# betaV2_0.net
KiCad netlist of a schematic drawn in Altium Designer
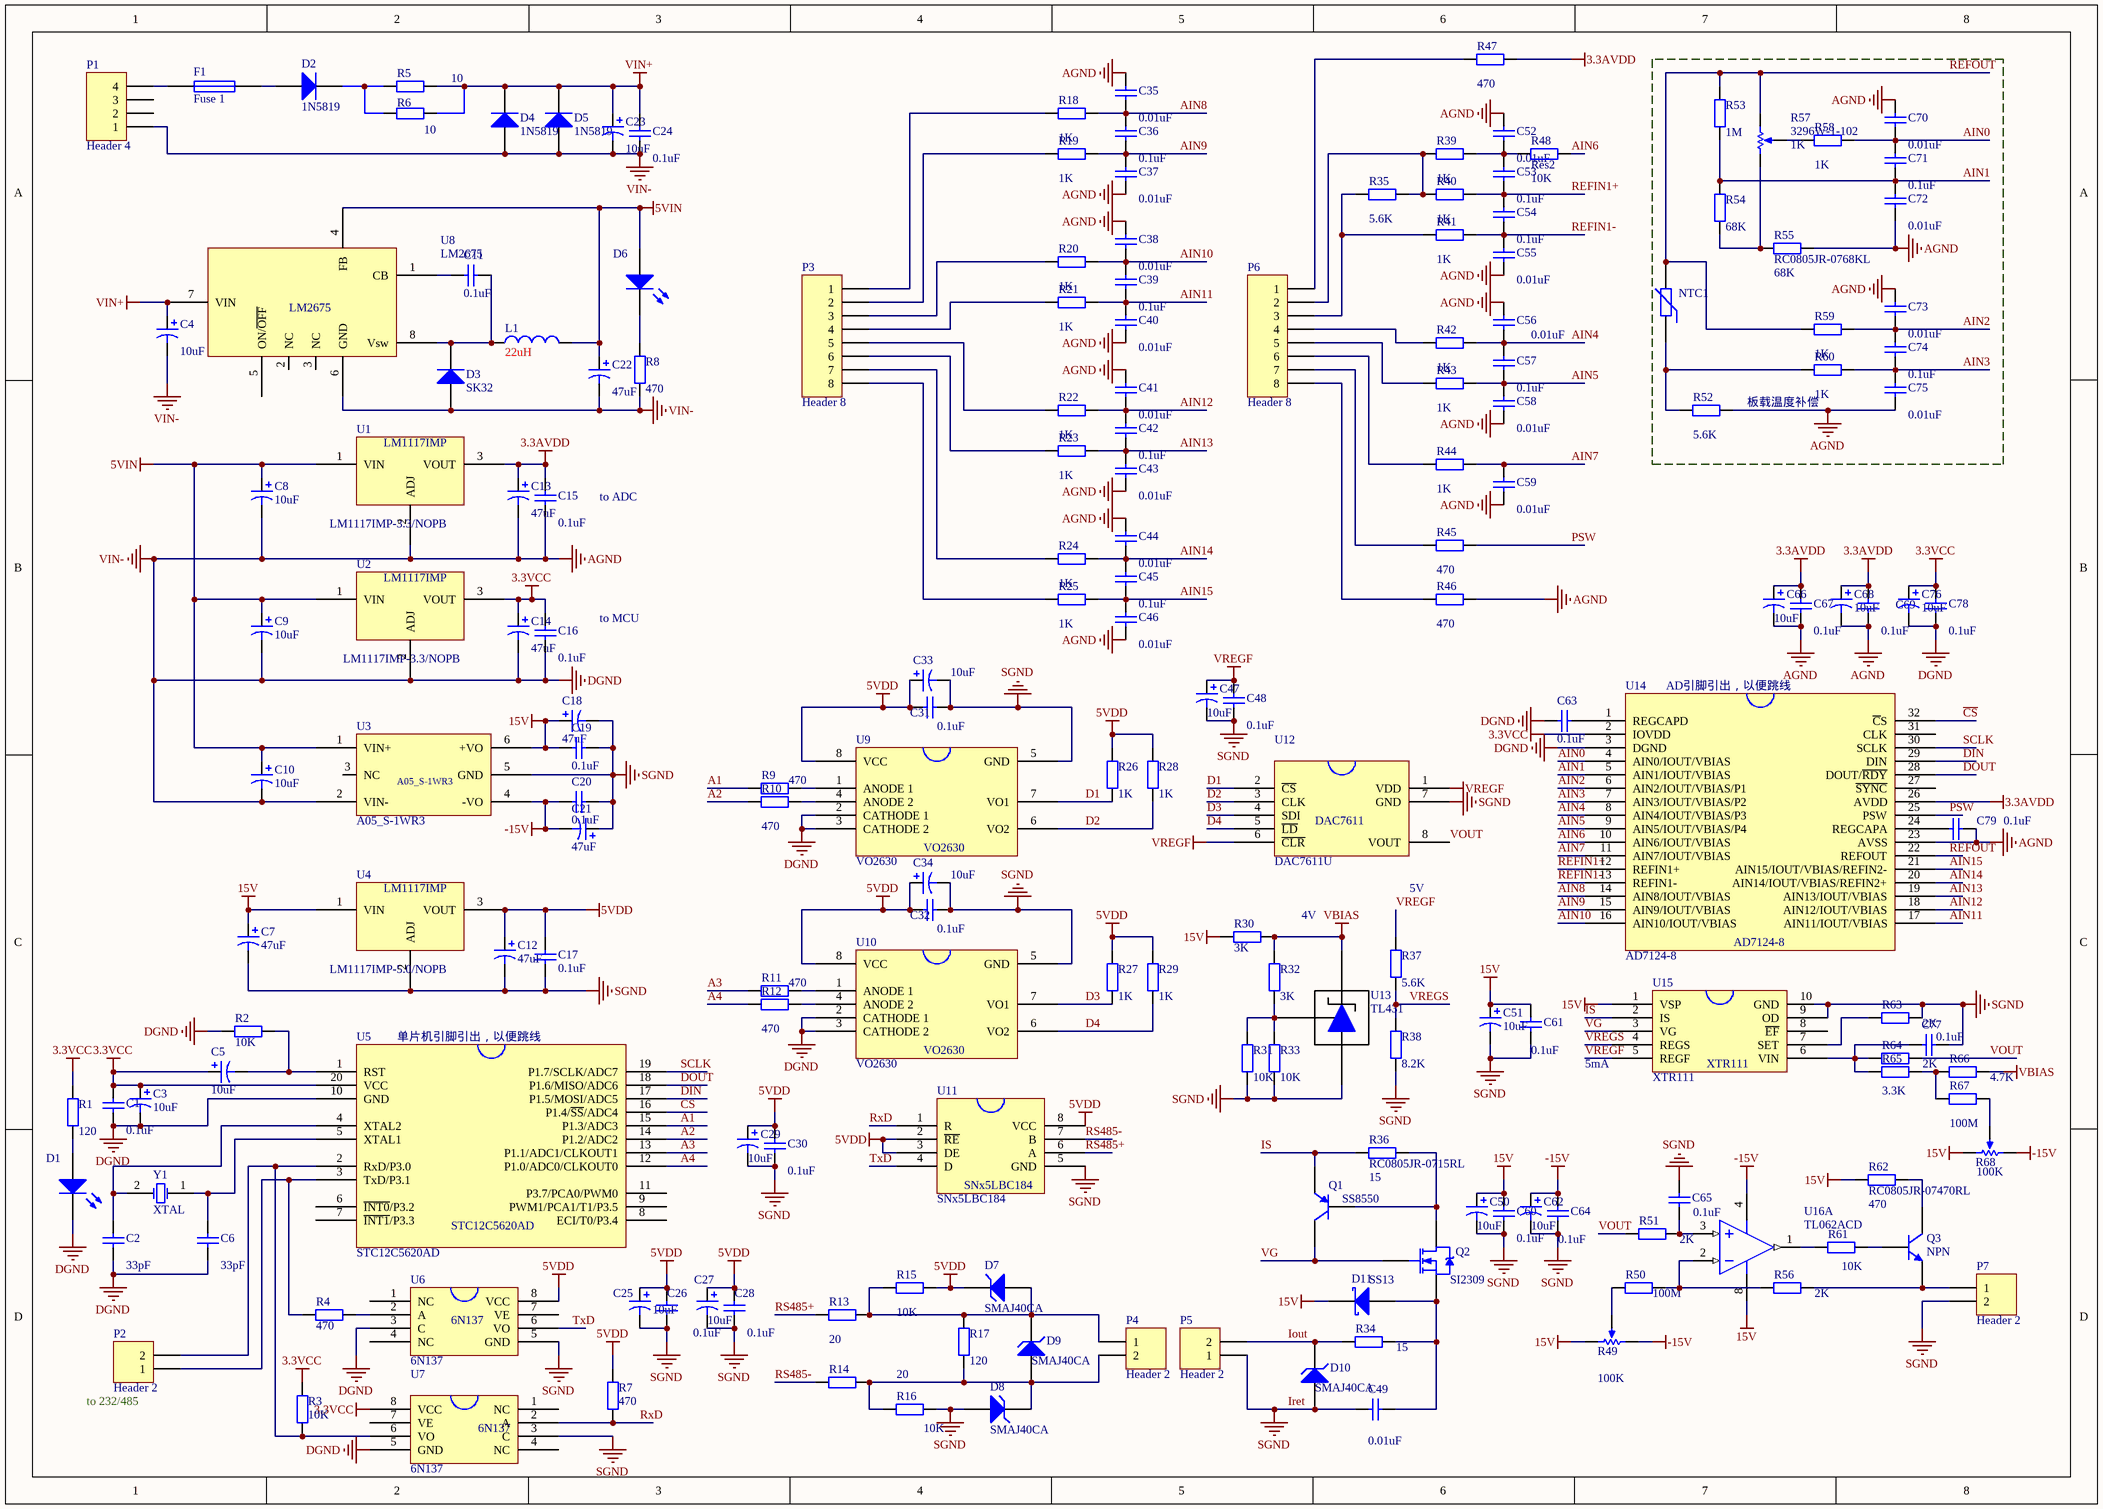
[diagram p0: betaV2.0.SchDoc]

(export (version "E")
  (design (tool "Eeschema 10.0.6"))
  (components
    (comp (ref "C1")
      (value "0.1uF")
      (footprint "0805c")
      (description "Capacitor")
      (fields (field (name "Comment") "CC0805MRX7R9BB104"))
      (libsource (lib "Miscellaneous Devices") (part "Cap"))
    )
    (comp (ref "C2")
      (value "33pF")
      (footprint "0805c")
      (description "Capacitor")
      (fields (field (name "Comment") "CC0805MRX7R9BB330") (field (name "PUBLISHER") "Altium Limited"))
      (libsource (lib "Miscellaneous Devices") (part "Cap"))
    )
    (comp (ref "C3")
      (value "10uF")
      (footprint "CB")
      (description "Polarized Capacitor (Radial)")
      (fields (field (name "Comment") "T494B106M010AHAUTO") (field (name "PUBLISHER") "Altium Limited"))
      (libsource (lib "Miscellaneous Devices") (part "Cap Pol1"))
    )
    (comp (ref "C4")
      (value "10uF")
      (footprint "Φ6.3×11.5")
      (description "Polarized Capacitor (Radial)")
      (fields (field (name "Comment") "ECR1VNP100M1V050011") (field (name "PUBLISHER") "Altium Limited"))
      (libsource (lib "Miscellaneous Devices") (part "Cap Pol1"))
    )
    (comp (ref "C5")
      (value "10uF")
      (footprint "CB")
      (description "Polarized Capacitor (Radial)")
      (fields (field (name "Comment") "T494B106M010AHAUTO") (field (name "PUBLISHER") "Altium Limited"))
      (libsource (lib "Miscellaneous Devices") (part "Cap Pol1"))
    )
    (comp (ref "C6")
      (value "33pF")
      (footprint "0805c")
      (description "Capacitor")
      (fields (field (name "Comment") "CC0805MRX7R9BB330") (field (name "PUBLISHER") "Altium Limited"))
      (libsource (lib "Miscellaneous Devices") (part "Cap"))
    )
    (comp (ref "C7")
      (value "47uF")
      (footprint "CB")
      (description "Polarized Capacitor (Radial)")
      (fields (field (name "Comment") "T494B476K025ATAUTO") (field (name "PUBLISHER") "Altium Limited"))
      (libsource (lib "Miscellaneous Devices") (part "Cap Pol1"))
    )
    (comp (ref "C8")
      (value "10uF")
      (footprint "CB")
      (description "Polarized Capacitor (Radial)")
      (fields (field (name "Comment") "T494B106M010AHAUTO") (field (name "PUBLISHER") "Altium Limited"))
      (libsource (lib "Miscellaneous Devices") (part "Cap Pol1"))
    )
    (comp (ref "C9")
      (value "10uF")
      (footprint "CB")
      (description "Polarized Capacitor (Radial)")
      (fields (field (name "Comment") "T494B106M010AHAUTO") (field (name "PUBLISHER") "Altium Limited"))
      (libsource (lib "Miscellaneous Devices") (part "Cap Pol1"))
    )
    (comp (ref "C10")
      (value "10uF")
      (footprint "CB")
      (description "Polarized Capacitor (Radial)")
      (fields (field (name "Comment") "T494B106M010AHAUTO") (field (name "PUBLISHER") "Altium Limited"))
      (libsource (lib "Miscellaneous Devices") (part "Cap Pol1"))
    )
    (comp (ref "C11")
      (value "0.1uF")
      (footprint "0805c")
      (description "Capacitor")
      (fields (field (name "Comment") "CC0805MRX7R9BB104") (field (name "PUBLISHER") "Altium Limited"))
      (libsource (lib "Miscellaneous Devices") (part "Cap"))
    )
    (comp (ref "C12")
      (value "47uF")
      (footprint "CB")
      (description "Polarized Capacitor (Radial)")
      (fields (field (name "Comment") "T494B476M010AHAUTO") (field (name "PUBLISHER") "Altium Limited"))
      (libsource (lib "Miscellaneous Devices") (part "Cap Pol1"))
    )
    (comp (ref "C13")
      (value "47uF")
      (footprint "CB")
      (description "Polarized Capacitor (Radial)")
      (fields (field (name "Comment") "T494B476M010AHAUTO") (field (name "PUBLISHER") "Altium Limited"))
      (libsource (lib "Miscellaneous Devices") (part "Cap Pol1"))
    )
    (comp (ref "C14")
      (value "47uF")
      (footprint "CB")
      (description "Polarized Capacitor (Radial)")
      (fields (field (name "Comment") "T494B476M010AHAUTO") (field (name "PUBLISHER") "Altium Limited"))
      (libsource (lib "Miscellaneous Devices") (part "Cap Pol1"))
    )
    (comp (ref "C15")
      (value "0.1uF")
      (footprint "0805c")
      (description "Capacitor")
      (fields (field (name "Comment") "CC0805MRX7R9BB104") (field (name "PUBLISHER") "Altium Limited"))
      (libsource (lib "Miscellaneous Devices") (part "Cap"))
    )
    (comp (ref "C16")
      (value "0.1uF")
      (footprint "0805c")
      (description "Capacitor")
      (fields (field (name "Comment") "CC0805MRX7R9BB104") (field (name "PUBLISHER") "Altium Limited"))
      (libsource (lib "Miscellaneous Devices") (part "Cap"))
    )
    (comp (ref "C17")
      (value "0.1uF")
      (footprint "0805c")
      (description "Capacitor")
      (fields (field (name "Comment") "CC0805MRX7R9BB104") (field (name "PUBLISHER") "Altium Limited"))
      (libsource (lib "Miscellaneous Devices") (part "Cap"))
    )
    (comp (ref "C18")
      (value "47uF")
      (footprint "CB")
      (description "Polarized Capacitor (Radial)")
      (fields (field (name "Comment") "T494B476K025ATAUTO") (field (name "PUBLISHER") "Altium Limited"))
      (libsource (lib "Miscellaneous Devices") (part "Cap Pol1"))
    )
    (comp (ref "C19")
      (value "0.1uF")
      (footprint "0805c")
      (description "Capacitor")
      (fields (field (name "Comment") "CC0805MRX7R9BB104") (field (name "PUBLISHER") "Altium Limited"))
      (libsource (lib "Miscellaneous Devices") (part "Cap"))
    )
    (comp (ref "C20")
      (value "0.1uF")
      (footprint "0805c")
      (description "Capacitor")
      (fields (field (name "Comment") "CC0805MRX7R9BB104") (field (name "PUBLISHER") "Altium Limited"))
      (libsource (lib "Miscellaneous Devices") (part "Cap"))
    )
    (comp (ref "C21")
      (value "47uF")
      (footprint "CB")
      (description "Polarized Capacitor (Radial)")
      (fields (field (name "Comment") "T494B476K025ATAUTO") (field (name "PUBLISHER") "Altium Limited"))
      (libsource (lib "Miscellaneous Devices") (part "Cap Pol1"))
    )
    (comp (ref "C22")
      (value "47uF")
      (footprint "CB")
      (description "Polarized Capacitor (Radial)")
      (fields (field (name "Comment") "T494B476M010AHAUTO") (field (name "PUBLISHER") "Altium Limited"))
      (libsource (lib "Miscellaneous Devices") (part "Cap Pol1"))
    )
    (comp (ref "C23")
      (value "10uF")
      (footprint "Φ6.3×11.5")
      (description "Polarized Capacitor (Radial)")
      (fields (field (name "Comment") "ECR1VNP100M1V050011") (field (name "PUBLISHER") "Altium Limited"))
      (libsource (lib "Miscellaneous Devices") (part "Cap Pol1"))
    )
    (comp (ref "C24")
      (value "0.1uF")
      (footprint "0805c")
      (description "Capacitor")
      (fields (field (name "Comment") "CC0805MRX7R9BB104") (field (name "PUBLISHER") "Altium Limited"))
      (libsource (lib "Miscellaneous Devices") (part "Cap"))
    )
    (comp (ref "C25")
      (value "10uF")
      (footprint "CB")
      (description "Polarized Capacitor (Radial)")
      (fields (field (name "Comment") "T494B106M010AHAUTO") (field (name "PUBLISHER") "Altium Limited"))
      (libsource (lib "Miscellaneous Devices") (part "Cap Pol1"))
    )
    (comp (ref "C26")
      (value "0.1uF")
      (footprint "0805c")
      (description "Capacitor")
      (fields (field (name "Comment") "CC0805MRX7R9BB104") (field (name "PUBLISHER") "Altium Limited"))
      (libsource (lib "Miscellaneous Devices") (part "Cap"))
    )
    (comp (ref "C27")
      (value "10uF")
      (footprint "CB")
      (description "Polarized Capacitor (Radial)")
      (fields (field (name "Comment") "T494B106M010AHAUTO") (field (name "PUBLISHER") "Altium Limited"))
      (libsource (lib "Miscellaneous Devices") (part "Cap Pol1"))
    )
    (comp (ref "C28")
      (value "0.1uF")
      (footprint "0805c")
      (description "Capacitor")
      (fields (field (name "Comment") "CC0805MRX7R9BB104") (field (name "PUBLISHER") "Altium Limited"))
      (libsource (lib "Miscellaneous Devices") (part "Cap"))
    )
    (comp (ref "C29")
      (value "10uF")
      (footprint "CB")
      (description "Polarized Capacitor (Radial)")
      (fields (field (name "Comment") "T494B106M010AHAUTO") (field (name "PUBLISHER") "Altium Limited"))
      (libsource (lib "Miscellaneous Devices") (part "Cap Pol1"))
    )
    (comp (ref "C30")
      (value "0.1uF")
      (footprint "0805c")
      (description "Capacitor")
      (fields (field (name "Comment") "CC0805MRX7R9BB104") (field (name "PUBLISHER") "Altium Limited"))
      (libsource (lib "Miscellaneous Devices") (part "Cap"))
    )
    (comp (ref "C31")
      (value "0.1uF")
      (footprint "0805c")
      (description "Capacitor")
      (fields (field (name "Comment") "CC0805MRX7R9BB104") (field (name "PUBLISHER") "Altium Limited"))
      (libsource (lib "Miscellaneous Devices") (part "Cap"))
    )
    (comp (ref "C32")
      (value "0.1uF")
      (footprint "0805c")
      (description "Capacitor")
      (fields (field (name "Comment") "CC0805MRX7R9BB104") (field (name "PUBLISHER") "Altium Limited"))
      (libsource (lib "Miscellaneous Devices") (part "Cap"))
    )
    (comp (ref "C33")
      (value "10uF")
      (footprint "CB")
      (description "Polarized Capacitor (Radial)")
      (fields (field (name "Comment") "T494B106M010AHAUTO") (field (name "PUBLISHER") "Altium Limited"))
      (libsource (lib "Miscellaneous Devices") (part "Cap Pol1"))
    )
    (comp (ref "C34")
      (value "10uF")
      (footprint "CB")
      (description "Polarized Capacitor (Radial)")
      (fields (field (name "Comment") "T494B106M010AHAUTO") (field (name "PUBLISHER") "Altium Limited"))
      (libsource (lib "Miscellaneous Devices") (part "Cap Pol1"))
    )
    (comp (ref "C35")
      (value "0.01uF")
      (footprint "0805c")
      (description "Capacitor")
      (fields (field (name "Comment") "CC0805MRX7R9BB103") (field (name "PUBLISHER") "Altium Limited"))
      (libsource (lib "Miscellaneous Devices") (part "Cap"))
    )
    (comp (ref "C36")
      (value "0.1uF")
      (footprint "0805c")
      (description "Capacitor")
      (fields (field (name "Comment") "CC0805MRX7R9BB104") (field (name "PUBLISHER") "Altium Limited"))
      (libsource (lib "Miscellaneous Devices") (part "Cap"))
    )
    (comp (ref "C37")
      (value "0.01uF")
      (footprint "0805c")
      (description "Capacitor")
      (fields (field (name "Comment") "CC0805MRX7R9BB103") (field (name "PUBLISHER") "Altium Limited"))
      (libsource (lib "Miscellaneous Devices") (part "Cap"))
    )
    (comp (ref "C38")
      (value "0.01uF")
      (footprint "0805c")
      (description "Capacitor")
      (fields (field (name "Comment") "CC0805MRX7R9BB103") (field (name "PUBLISHER") "Altium Limited"))
      (libsource (lib "Miscellaneous Devices") (part "Cap"))
    )
    (comp (ref "C39")
      (value "0.1uF")
      (footprint "0805c")
      (description "Capacitor")
      (fields (field (name "Comment") "CC0805MRX7R9BB104") (field (name "PUBLISHER") "Altium Limited"))
      (libsource (lib "Miscellaneous Devices") (part "Cap"))
    )
    (comp (ref "C40")
      (value "0.01uF")
      (footprint "0805c")
      (description "Capacitor")
      (fields (field (name "Comment") "CC0805MRX7R9BB103") (field (name "PUBLISHER") "Altium Limited"))
      (libsource (lib "Miscellaneous Devices") (part "Cap"))
    )
    (comp (ref "C41")
      (value "0.01uF")
      (footprint "0805c")
      (description "Capacitor")
      (fields (field (name "Comment") "CC0805MRX7R9BB103") (field (name "PUBLISHER") "Altium Limited"))
      (libsource (lib "Miscellaneous Devices") (part "Cap"))
    )
    (comp (ref "C42")
      (value "0.1uF")
      (footprint "0805c")
      (description "Capacitor")
      (fields (field (name "Comment") "CC0805MRX7R9BB104") (field (name "PUBLISHER") "Altium Limited"))
      (libsource (lib "Miscellaneous Devices") (part "Cap"))
    )
    (comp (ref "C43")
      (value "0.01uF")
      (footprint "0805c")
      (description "Capacitor")
      (fields (field (name "Comment") "CC0805MRX7R9BB103") (field (name "PUBLISHER") "Altium Limited"))
      (libsource (lib "Miscellaneous Devices") (part "Cap"))
    )
    (comp (ref "C44")
      (value "0.01uF")
      (footprint "0805c")
      (description "Capacitor")
      (fields (field (name "Comment") "CC0805MRX7R9BB103") (field (name "PUBLISHER") "Altium Limited"))
      (libsource (lib "Miscellaneous Devices") (part "Cap"))
    )
    (comp (ref "C45")
      (value "0.1uF")
      (footprint "0805c")
      (description "Capacitor")
      (fields (field (name "Comment") "CC0805MRX7R9BB104") (field (name "PUBLISHER") "Altium Limited"))
      (libsource (lib "Miscellaneous Devices") (part "Cap"))
    )
    (comp (ref "C46")
      (value "0.01uF")
      (footprint "0805c")
      (description "Capacitor")
      (fields (field (name "Comment") "CC0805MRX7R9BB103") (field (name "PUBLISHER") "Altium Limited"))
      (libsource (lib "Miscellaneous Devices") (part "Cap"))
    )
    (comp (ref "C47")
      (value "10uF")
      (footprint "CB")
      (description "Polarized Capacitor (Radial)")
      (fields (field (name "Comment") "T494B106M010AHAUTO") (field (name "PUBLISHER") "Altium Limited"))
      (libsource (lib "Miscellaneous Devices") (part "Cap Pol1"))
    )
    (comp (ref "C48")
      (value "0.1uF")
      (footprint "0805c")
      (description "Capacitor")
      (fields (field (name "Comment") "CC0805MRX7R9BB104") (field (name "PUBLISHER") "Altium Limited"))
      (libsource (lib "Miscellaneous Devices") (part "Cap"))
    )
    (comp (ref "C49")
      (value "0.01uF")
      (footprint "0805c")
      (description "Capacitor")
      (fields (field (name "Comment") "CC0805MRX7R9BB103") (field (name "PUBLISHER") "Altium Limited"))
      (libsource (lib "Miscellaneous Devices") (part "Cap"))
    )
    (comp (ref "C50")
      (value "10uF")
      (footprint "CB")
      (description "Polarized Capacitor (Radial)")
      (fields (field (name "Comment") "T494B106M025AHAUTO") (field (name "PUBLISHER") "Altium Limited"))
      (libsource (lib "Miscellaneous Devices") (part "Cap Pol1"))
    )
    (comp (ref "C51")
      (value "10uF")
      (footprint "CB")
      (description "Polarized Capacitor (Radial)")
      (fields (field (name "Comment") "T494B106M025AHAUTO") (field (name "PUBLISHER") "Altium Limited"))
      (libsource (lib "Miscellaneous Devices") (part "Cap Pol1"))
    )
    (comp (ref "C52")
      (value "0.01uF")
      (footprint "0805c")
      (description "Capacitor")
      (fields (field (name "Comment") "CC0805MRX7R9BB103") (field (name "PUBLISHER") "Altium Limited"))
      (libsource (lib "Miscellaneous Devices") (part "Cap"))
    )
    (comp (ref "C53")
      (value "0.1uF")
      (footprint "0805c")
      (description "Capacitor")
      (fields (field (name "Comment") "CC0805MRX7R9BB104") (field (name "PUBLISHER") "Altium Limited"))
      (libsource (lib "Miscellaneous Devices") (part "Cap"))
    )
    (comp (ref "C54")
      (value "0.1uF")
      (footprint "0805c")
      (description "Capacitor")
      (fields (field (name "Comment") "CC0805MRX7R9BB104") (field (name "PUBLISHER") "Altium Limited"))
      (libsource (lib "Miscellaneous Devices") (part "Cap"))
    )
    (comp (ref "C55")
      (value "0.01uF")
      (footprint "0805c")
      (description "Capacitor")
      (fields (field (name "Comment") "CC0805MRX7R9BB103") (field (name "PUBLISHER") "Altium Limited"))
      (libsource (lib "Miscellaneous Devices") (part "Cap"))
    )
    (comp (ref "C56")
      (value "0.01uF")
      (footprint "0805c")
      (description "Capacitor")
      (fields (field (name "Comment") "CC0805MRX7R9BB103") (field (name "PUBLISHER") "Altium Limited"))
      (libsource (lib "Miscellaneous Devices") (part "Cap"))
    )
    (comp (ref "C57")
      (value "0.1uF")
      (footprint "0805c")
      (description "Capacitor")
      (fields (field (name "Comment") "CC0805MRX7R9BB104") (field (name "PUBLISHER") "Altium Limited"))
      (libsource (lib "Miscellaneous Devices") (part "Cap"))
    )
    (comp (ref "C58")
      (value "0.01uF")
      (footprint "0805c")
      (description "Capacitor")
      (fields (field (name "Comment") "CC0805MRX7R9BB103") (field (name "PUBLISHER") "Altium Limited"))
      (libsource (lib "Miscellaneous Devices") (part "Cap"))
    )
    (comp (ref "C59")
      (value "0.01uF")
      (footprint "0805c")
      (description "Capacitor")
      (fields (field (name "Comment") "CC0805MRX7R9BB103") (field (name "PUBLISHER") "Altium Limited"))
      (libsource (lib "Miscellaneous Devices") (part "Cap"))
    )
    (comp (ref "C60")
      (value "0.1uF")
      (footprint "0805c")
      (description "Capacitor")
      (fields (field (name "Comment") "CC0805MRX7R9BB104") (field (name "PUBLISHER") "Altium Limited"))
      (libsource (lib "Miscellaneous Devices") (part "Cap"))
    )
    (comp (ref "C61")
      (value "0.1uF")
      (footprint "0805c")
      (description "Capacitor")
      (fields (field (name "Comment") "CC0805MRX7R9BB104") (field (name "PUBLISHER") "Altium Limited"))
      (libsource (lib "Miscellaneous Devices") (part "Cap"))
    )
    (comp (ref "C62")
      (value "10uF")
      (footprint "CB")
      (description "Polarized Capacitor (Radial)")
      (fields (field (name "Comment") "T494B106M025AHAUTO") (field (name "PUBLISHER") "Altium Limited"))
      (libsource (lib "Miscellaneous Devices") (part "Cap Pol1"))
    )
    (comp (ref "C63")
      (value "0.1uF")
      (footprint "0805c")
      (description "Capacitor")
      (fields (field (name "Comment") "CC0805MRX7R9BB104") (field (name "PUBLISHER") "Altium Limited"))
      (libsource (lib "Miscellaneous Devices") (part "Cap"))
    )
    (comp (ref "C64")
      (value "0.1uF")
      (footprint "0805c")
      (description "Capacitor")
      (fields (field (name "Comment") "CC0805MRX7R9BB104") (field (name "PUBLISHER") "Altium Limited"))
      (libsource (lib "Miscellaneous Devices") (part "Cap"))
    )
    (comp (ref "C65")
      (value "0.1uF")
      (footprint "0805c")
      (description "Capacitor")
      (fields (field (name "Comment") "CC0805MRX7R9BB104") (field (name "PUBLISHER") "Altium Limited"))
      (libsource (lib "Miscellaneous Devices") (part "Cap"))
    )
    (comp (ref "C66")
      (value "10uF")
      (footprint "CB")
      (description "Polarized Capacitor (Radial)")
      (fields (field (name "Comment") "T494B106M010AHAUTO") (field (name "PUBLISHER") "Altium Limited"))
      (libsource (lib "Miscellaneous Devices") (part "Cap Pol1"))
    )
    (comp (ref "C67")
      (value "0.1uF")
      (footprint "0805c")
      (description "Capacitor")
      (fields (field (name "Comment") "CC0805MRX7R9BB104") (field (name "PUBLISHER") "Altium Limited"))
      (libsource (lib "Miscellaneous Devices") (part "Cap"))
    )
    (comp (ref "C68")
      (value "10uF")
      (footprint "CB")
      (description "Polarized Capacitor (Radial)")
      (fields (field (name "Comment") "T494B106M010AHAUTO") (field (name "PUBLISHER") "Altium Limited"))
      (libsource (lib "Miscellaneous Devices") (part "Cap Pol1"))
    )
    (comp (ref "C69")
      (value "0.1uF")
      (footprint "0805c")
      (description "Capacitor")
      (fields (field (name "Comment") "CC0805MRX7R9BB104") (field (name "PUBLISHER") "Altium Limited"))
      (libsource (lib "Miscellaneous Devices") (part "Cap"))
    )
    (comp (ref "C70")
      (value "0.01uF")
      (footprint "0805c")
      (description "Capacitor")
      (fields (field (name "Comment") "CC0805MRX7R9BB103") (field (name "PUBLISHER") "Altium Limited"))
      (libsource (lib "Miscellaneous Devices") (part "Cap"))
    )
    (comp (ref "C71")
      (value "0.1uF")
      (footprint "0805c")
      (description "Capacitor")
      (fields (field (name "Comment") "CC0805MRX7R9BB104") (field (name "PUBLISHER") "Altium Limited"))
      (libsource (lib "Miscellaneous Devices") (part "Cap"))
    )
    (comp (ref "C72")
      (value "0.01uF")
      (footprint "0805c")
      (description "Capacitor")
      (fields (field (name "Comment") "CC0805MRX7R9BB103") (field (name "PUBLISHER") "Altium Limited"))
      (libsource (lib "Miscellaneous Devices") (part "Cap"))
    )
    (comp (ref "C73")
      (value "0.01uF")
      (footprint "0805c")
      (description "Capacitor")
      (fields (field (name "Comment") "CC0805MRX7R9BB103") (field (name "PUBLISHER") "Altium Limited"))
      (libsource (lib "Miscellaneous Devices") (part "Cap"))
    )
    (comp (ref "C74")
      (value "0.1uF")
      (footprint "0805c")
      (description "Capacitor")
      (fields (field (name "Comment") "CC0805MRX7R9BB104") (field (name "PUBLISHER") "Altium Limited"))
      (libsource (lib "Miscellaneous Devices") (part "Cap"))
    )
    (comp (ref "C75")
      (value "0.01uF")
      (footprint "0805c")
      (description "Capacitor")
      (fields (field (name "Comment") "CC0805MRX7R9BB103") (field (name "PUBLISHER") "Altium Limited"))
      (libsource (lib "Miscellaneous Devices") (part "Cap"))
    )
    (comp (ref "C76")
      (value "10uF")
      (footprint "CB")
      (description "Polarized Capacitor (Radial)")
      (fields (field (name "Comment") "T494B106M010AHAUTO") (field (name "PUBLISHER") "Altium Limited"))
      (libsource (lib "Miscellaneous Devices") (part "Cap Pol1"))
    )
    (comp (ref "C77")
      (value "0.1uF")
      (footprint "0805c")
      (description "Capacitor")
      (fields (field (name "Comment") "CC0805MRX7R9BB104") (field (name "PUBLISHER") "Altium Limited"))
      (libsource (lib "Miscellaneous Devices") (part "Cap"))
    )
    (comp (ref "C78")
      (value "0.1uF")
      (footprint "0805c")
      (description "Capacitor")
      (fields (field (name "Comment") "CC0805MRX7R9BB104") (field (name "PUBLISHER") "Altium Limited"))
      (libsource (lib "Miscellaneous Devices") (part "Cap"))
    )
    (comp (ref "C79")
      (value "0.1uF")
      (footprint "0805c")
      (description "Capacitor")
      (fields (field (name "Comment") "CC0805MRX7R9BB104") (field (name "PUBLISHER") "Altium Limited"))
      (libsource (lib "Miscellaneous Devices") (part "Cap"))
    )
    (comp (ref "D1")
      (value "150080GS75000")
      (footprint "6-0805_N")
      (description "Typical RED, GREEN, YELLOW, AMBER GaAs LED")
      (fields (field (name "PUBLISHER") "Altium Limited"))
      (libsource (lib "Miscellaneous Devices") (part "LED2"))
    )
    (comp (ref "D2")
      (value "1N5819")
      (footprint "SMC")
      (description "Default Diode")
      (fields (field (name "PUBLISHER") "Altium Limited"))
      (libsource (lib "Miscellaneous Devices") (part "Diode"))
    )
    (comp (ref "D3")
      (value "SK32")
      (footprint "SMC")
      (description "Default Diode")
      (fields (field (name "PUBLISHER") "Altium Limited"))
      (libsource (lib "Miscellaneous Devices") (part "Diode"))
    )
    (comp (ref "D4")
      (value "1N5819")
      (footprint "SMC")
      (description "Default Diode")
      (fields (field (name "PUBLISHER") "Altium Limited"))
      (libsource (lib "Miscellaneous Devices") (part "Diode"))
    )
    (comp (ref "D5")
      (value "1N5819")
      (footprint "SMC")
      (description "Default Diode")
      (fields (field (name "PUBLISHER") "Altium Limited"))
      (libsource (lib "Miscellaneous Devices") (part "Diode"))
    )
    (comp (ref "D6")
      (value "150080GS75000")
      (footprint "LEDΦ3.0")
      (description "Typical RED, GREEN, YELLOW, AMBER GaAs LED")
      (fields (field (name "PUBLISHER") "Altium Limited"))
      (libsource (lib "Miscellaneous Devices") (part "LED2"))
    )
    (comp (ref "D7")
      (value "SMAJ40CA")
      (footprint "SMB")
      (description "Zener Diode")
      (fields (field (name "PUBLISHER") "Altium Limited"))
      (libsource (lib "Miscellaneous Devices") (part "D Zener"))
    )
    (comp (ref "D8")
      (value "SMAJ40CA")
      (footprint "SMB")
      (description "Zener Diode")
      (fields (field (name "PUBLISHER") "Altium Limited"))
      (libsource (lib "Miscellaneous Devices") (part "D Zener"))
    )
    (comp (ref "D9")
      (value "SMAJ40CA")
      (footprint "SMB")
      (description "Zener Diode")
      (fields (field (name "PUBLISHER") "Altium Limited"))
      (libsource (lib "Miscellaneous Devices") (part "D Zener"))
    )
    (comp (ref "D10")
      (value "SMAJ40CA")
      (footprint "SMB")
      (description "Zener Diode")
      (fields (field (name "PUBLISHER") "Altium Limited"))
      (libsource (lib "Miscellaneous Devices") (part "D Zener"))
    )
    (comp (ref "D11")
      (value "SS13")
      (footprint "SMB")
      (description "Schottky Diode")
      (fields (field (name "PUBLISHER") "Altium Limited"))
      (libsource (lib "Miscellaneous Devices") (part "D Schottky"))
    )
    (comp (ref "F1")
      (value "Fuse 1")
      (footprint "6-0805_L")
      (description "Fuse")
      (fields (field (name "PUBLISHER") "Altium Limited"))
      (libsource (lib "Miscellaneous Devices") (part "Fuse 1"))
    )
    (comp (ref "L1")
      (value "22uH")
      (footprint "vls4012")
      (fields (field (name "Comment") "VLS4012HBX-220M"))
      (libsource (lib "Miscellaneous Devices") (part "Inductor"))
    )
    (comp (ref "NTC1")
      (value "NTCS0805E3103JHT")
      (footprint "6-0805_N")
      (description "Varistor (Voltage-Sensitive Resistor)")
      (fields (field (name "PUBLISHER") "Altium Limited"))
      (libsource (lib "Miscellaneous Devices") (part "Res Varistor"))
    )
    (comp (ref "P1")
      (value "Header 4")
      (footprint "HDR1X4")
      (description "Header, 4-Pin")
      (fields (field (name "PUBLISHER") "Altium Limited"))
      (libsource (lib "Miscellaneous Connectors") (part "Header 4"))
    )
    (comp (ref "P2")
      (value "Header 2")
      (footprint "HDR1X2")
      (description "Header, 2-Pin")
      (fields (field (name "PUBLISHER") "Altium Limited"))
      (libsource (lib "") (part "Header 2_1"))
    )
    (comp (ref "P3")
      (value "Header 8")
      (footprint "HDR1X8")
      (description "Header, 8-Pin")
      (fields (field (name "PUBLISHER") "Altium Limited"))
      (libsource (lib "Miscellaneous Connectors") (part "Header 8"))
    )
    (comp (ref "P4")
      (value "Header 2")
      (footprint "HDR1X2")
      (description "Header, 2-Pin")
      (fields (field (name "PUBLISHER") "Altium Limited"))
      (libsource (lib "Miscellaneous Connectors") (part "Header 2"))
    )
    (comp (ref "P5")
      (value "Header 2")
      (footprint "HDR1X2")
      (description "Header, 2-Pin")
      (fields (field (name "PUBLISHER") "Altium Limited"))
      (libsource (lib "") (part "Header 2_1"))
    )
    (comp (ref "P6")
      (value "Header 8")
      (footprint "HDR1X8")
      (description "Header, 8-Pin")
      (fields (field (name "PUBLISHER") "Altium Limited"))
      (libsource (lib "Miscellaneous Connectors") (part "Header 8"))
    )
    (comp (ref "P7")
      (value "Header 2")
      (footprint "HDR1X2")
      (description "Header, 2-Pin")
      (fields (field (name "PUBLISHER") "Altium Limited"))
      (libsource (lib "Miscellaneous Connectors") (part "Header 2"))
    )
    (comp (ref "Q1")
      (value "SS8550")
      (footprint "SOT-23-BJT")
      (description "PNP Bipolar Transistor")
      (fields (field (name "PUBLISHER") "Altium Limited"))
      (libsource (lib "Miscellaneous Devices") (part "PNP"))
    )
    (comp (ref "Q2")
      (value "SI2309")
      (footprint "SOT-23-MOS")
      (description "N-Channel Power MOSFET")
      (fields (field (name "PUBLISHER") "Altium Limited"))
      (libsource (lib "Miscellaneous Devices") (part "NMOS-2"))
    )
    (comp (ref "Q3")
      (value "NPN")
      (footprint "SOT-23-BJT")
      (description "NPN Bipolar Transistor")
      (fields (field (name "PUBLISHER") "Altium Limited"))
      (libsource (lib "Miscellaneous Devices") (part "NPN"))
    )
    (comp (ref "R1")
      (value "120")
      (footprint "0805R")
      (description "Resistor")
      (fields (field (name "Comment") "RC0805JR-07120RL") (field (name "PUBLISHER") "Altium Limited"))
      (libsource (lib "") (part "Res2_1"))
    )
    (comp (ref "R2")
      (value "10K")
      (footprint "0805R")
      (description "Resistor")
      (fields (field (name "Comment") "RC0805JR-0710KL") (field (name "PUBLISHER") "Altium Limited"))
      (libsource (lib "") (part "Res2_3"))
    )
    (comp (ref "R3")
      (value "10K")
      (footprint "0805R")
      (description "Resistor")
      (fields (field (name "Comment") "RC0805JR-0710KRL") (field (name "PUBLISHER") "Altium Limited"))
      (libsource (lib "") (part "Res2_2"))
    )
    (comp (ref "R4")
      (value "470")
      (footprint "0805R")
      (description "Resistor")
      (fields (field (name "Comment") "RC0805JR-07470RL") (field (name "PUBLISHER") "Altium Limited"))
      (libsource (lib "") (part "Res2_3"))
    )
    (comp (ref "R5")
      (value "10")
      (footprint "0805R")
      (description "Resistor")
      (fields (field (name "Comment") "PNP-200KJBJ26-10R") (field (name "PUBLISHER") "Altium Limited"))
      (libsource (lib "Miscellaneous Devices") (part "Res2"))
    )
    (comp (ref "R6")
      (value "10")
      (footprint "0805R")
      (description "Resistor")
      (fields (field (name "Comment") "PNP-200KJBJ26-10R") (field (name "PUBLISHER") "Altium Limited"))
      (libsource (lib "Miscellaneous Devices") (part "Res2"))
    )
    (comp (ref "R7")
      (value "470")
      (footprint "0805R")
      (description "Resistor")
      (fields (field (name "Comment") "RC0805JR-07470RL") (field (name "PUBLISHER") "Altium Limited"))
      (libsource (lib "") (part "Res2_2"))
    )
    (comp (ref "R8")
      (value "470")
      (footprint "0805R")
      (description "Resistor")
      (fields (field (name "Comment") "RC0805JR-07470RL") (field (name "PUBLISHER") "Altium Limited"))
      (libsource (lib "") (part "Res2_2"))
    )
    (comp (ref "R9")
      (value "470")
      (footprint "0805R")
      (description "Resistor")
      (fields (field (name "Comment") "RC0805JR-07470RL") (field (name "PUBLISHER") "Altium Limited"))
      (libsource (lib "Miscellaneous Devices") (part "Res2"))
    )
    (comp (ref "R10")
      (value "470")
      (footprint "0805R")
      (description "Resistor")
      (fields (field (name "Comment") "RC0805JR-07470RL") (field (name "PUBLISHER") "Altium Limited"))
      (libsource (lib "Miscellaneous Devices") (part "Res2"))
    )
    (comp (ref "R11")
      (value "470")
      (footprint "0805R")
      (description "Resistor")
      (fields (field (name "Comment") "RC0805JR-07470RL") (field (name "PUBLISHER") "Altium Limited"))
      (libsource (lib "Miscellaneous Devices") (part "Res2"))
    )
    (comp (ref "R12")
      (value "470")
      (footprint "0805R")
      (description "Resistor")
      (fields (field (name "Comment") "RC0805JR-07470RL") (field (name "PUBLISHER") "Altium Limited"))
      (libsource (lib "Miscellaneous Devices") (part "Res2"))
    )
    (comp (ref "R13")
      (value "20")
      (footprint "0805R")
      (description "Resistor")
      (fields (field (name "Comment") "RC0805JR-0720RL") (field (name "PUBLISHER") "Altium Limited"))
      (libsource (lib "") (part "Res2_3"))
    )
    (comp (ref "R14")
      (value "20")
      (footprint "0805R")
      (description "Resistor")
      (fields (field (name "Comment") "RC0805JR-0720RL") (field (name "PUBLISHER") "Altium Limited"))
      (libsource (lib "Miscellaneous Devices") (part "Res2"))
    )
    (comp (ref "R15")
      (value "10K")
      (footprint "0805R")
      (description "Resistor")
      (fields (field (name "Comment") "RC0805JR-0710KL") (field (name "PUBLISHER") "Altium Limited"))
      (libsource (lib "Miscellaneous Devices") (part "Res2"))
    )
    (comp (ref "R16")
      (value "10K")
      (footprint "0805R")
      (description "Resistor")
      (fields (field (name "Comment") "RC0805JR-0710KL") (field (name "PUBLISHER") "Altium Limited"))
      (libsource (lib "Miscellaneous Devices") (part "Res2"))
    )
    (comp (ref "R17")
      (value "120")
      (footprint "0805R")
      (description "Resistor")
      (fields (field (name "Comment") "RC0805JR-07120RL") (field (name "PUBLISHER") "Altium Limited"))
      (libsource (lib "") (part "Res2_2"))
    )
    (comp (ref "R18")
      (value "1K")
      (footprint "0805R")
      (description "Resistor")
      (fields (field (name "Comment") "RC0805JR-071KL") (field (name "PUBLISHER") "Altium Limited"))
      (libsource (lib "Miscellaneous Devices") (part "Res2"))
    )
    (comp (ref "R19")
      (value "1K")
      (footprint "0805R")
      (description "Resistor")
      (fields (field (name "Comment") "RC0805JR-071KL") (field (name "PUBLISHER") "Altium Limited"))
      (libsource (lib "Miscellaneous Devices") (part "Res2"))
    )
    (comp (ref "R20")
      (value "1K")
      (footprint "0805R")
      (description "Resistor")
      (fields (field (name "Comment") "RC0805JR-071KL") (field (name "PUBLISHER") "Altium Limited"))
      (libsource (lib "Miscellaneous Devices") (part "Res2"))
    )
    (comp (ref "R21")
      (value "1K")
      (footprint "0805R")
      (description "Resistor")
      (fields (field (name "Comment") "RC0805JR-071KL") (field (name "PUBLISHER") "Altium Limited"))
      (libsource (lib "Miscellaneous Devices") (part "Res2"))
    )
    (comp (ref "R22")
      (value "1K")
      (footprint "0805R")
      (description "Resistor")
      (fields (field (name "Comment") "RC0805JR-071KL") (field (name "PUBLISHER") "Altium Limited"))
      (libsource (lib "Miscellaneous Devices") (part "Res2"))
    )
    (comp (ref "R23")
      (value "1K")
      (footprint "0805R")
      (description "Resistor")
      (fields (field (name "Comment") "RC0805JR-071KL") (field (name "PUBLISHER") "Altium Limited"))
      (libsource (lib "Miscellaneous Devices") (part "Res2"))
    )
    (comp (ref "R24")
      (value "1K")
      (footprint "0805R")
      (description "Resistor")
      (fields (field (name "Comment") "RC0805JR-071KL") (field (name "PUBLISHER") "Altium Limited"))
      (libsource (lib "Miscellaneous Devices") (part "Res2"))
    )
    (comp (ref "R25")
      (value "1K")
      (footprint "0805R")
      (description "Resistor")
      (fields (field (name "Comment") "RC0805JR-071KL") (field (name "PUBLISHER") "Altium Limited"))
      (libsource (lib "Miscellaneous Devices") (part "Res2"))
    )
    (comp (ref "R26")
      (value "1K")
      (footprint "0805R")
      (description "Resistor")
      (fields (field (name "Comment") "RC0805JR-071KL") (field (name "PUBLISHER") "Altium Limited"))
      (libsource (lib "") (part "Res2_1"))
    )
    (comp (ref "R27")
      (value "1K")
      (footprint "0805R")
      (description "Resistor")
      (fields (field (name "Comment") "RC0805JR-071KL") (field (name "PUBLISHER") "Altium Limited"))
      (libsource (lib "") (part "Res2_1"))
    )
    (comp (ref "R28")
      (value "1K")
      (footprint "0805R")
      (description "Resistor")
      (fields (field (name "Comment") "RC0805JR-071KL") (field (name "PUBLISHER") "Altium Limited"))
      (libsource (lib "") (part "Res2_1"))
    )
    (comp (ref "R29")
      (value "1K")
      (footprint "0805R")
      (description "Resistor")
      (fields (field (name "Comment") "RC0805JR-071KL") (field (name "PUBLISHER") "Altium Limited"))
      (libsource (lib "") (part "Res2_1"))
    )
    (comp (ref "R30")
      (value "3K")
      (footprint "0805R")
      (description "Resistor")
      (fields (field (name "Comment") "RC0805JR-073KL") (field (name "PUBLISHER") "Altium Limited"))
      (libsource (lib "") (part "Res2_3"))
    )
    (comp (ref "R31")
      (value "10K")
      (footprint "0805R")
      (description "Resistor")
      (fields (field (name "Comment") "RC0805JR-0710KL") (field (name "PUBLISHER") "Altium Limited"))
      (libsource (lib "") (part "Res2_1"))
    )
    (comp (ref "R32")
      (value "3K")
      (footprint "0805R")
      (description "Resistor")
      (fields (field (name "Comment") "RC0805JR-073KL") (field (name "PUBLISHER") "Altium Limited"))
      (libsource (lib "") (part "Res2_1"))
    )
    (comp (ref "R33")
      (value "10K")
      (footprint "0805R")
      (description "Resistor")
      (fields (field (name "Comment") "RC0805JR-0710KL") (field (name "PUBLISHER") "Altium Limited"))
      (libsource (lib "") (part "Res2_1"))
    )
    (comp (ref "R34")
      (value "15")
      (footprint "0805R")
      (description "Resistor")
      (fields (field (name "Comment") "RC0805JR-0715RL") (field (name "PUBLISHER") "Altium Limited"))
      (libsource (lib "") (part "Res2_3"))
    )
    (comp (ref "R35")
      (value "5.6K")
      (footprint "0805R")
      (description "Resistor")
      (fields (field (name "Comment") "RC0805JR-075600RL") (field (name "PUBLISHER") "Altium Limited"))
      (libsource (lib "") (part "Res2_3"))
    )
    (comp (ref "R36")
      (value "RC0805JR-0715RL")
      (footprint "0805R")
      (description "Resistor")
      (fields (field (name "ALTIUM_VALUE") "15") (field (name "PUBLISHER") "Altium Limited"))
      (libsource (lib "Miscellaneous Devices") (part "Res2"))
    )
    (comp (ref "R37")
      (value "5.6K")
      (footprint "0805R")
      (description "Resistor")
      (fields (field (name "Comment") "RC0805JR-075600RL") (field (name "PUBLISHER") "Altium Limited"))
      (libsource (lib "") (part "Res2_1"))
    )
    (comp (ref "R38")
      (value "8.2K")
      (footprint "0805R")
      (description "Resistor")
      (fields (field (name "Comment") "RC0805JR-078200RL") (field (name "PUBLISHER") "Altium Limited"))
      (libsource (lib "") (part "Res2_1"))
    )
    (comp (ref "R39")
      (value "1K")
      (footprint "0805R")
      (description "Resistor")
      (fields (field (name "Comment") "RC0805JR-071KL") (field (name "PUBLISHER") "Altium Limited"))
      (libsource (lib "Miscellaneous Devices") (part "Res2"))
    )
    (comp (ref "R40")
      (value "1K")
      (footprint "0805R")
      (description "Resistor")
      (fields (field (name "Comment") "RC0805JR-071KL") (field (name "PUBLISHER") "Altium Limited"))
      (libsource (lib "Miscellaneous Devices") (part "Res2"))
    )
    (comp (ref "R41")
      (value "1K")
      (footprint "0805R")
      (description "Resistor")
      (fields (field (name "Comment") "RC0805JR-071KL") (field (name "PUBLISHER") "Altium Limited"))
      (libsource (lib "Miscellaneous Devices") (part "Res2"))
    )
    (comp (ref "R42")
      (value "1K")
      (footprint "0805R")
      (description "Resistor")
      (fields (field (name "Comment") "RC0805JR-071KL") (field (name "PUBLISHER") "Altium Limited"))
      (libsource (lib "Miscellaneous Devices") (part "Res2"))
    )
    (comp (ref "R43")
      (value "1K")
      (footprint "0805R")
      (description "Resistor")
      (fields (field (name "Comment") "RC0805JR-071KL") (field (name "PUBLISHER") "Altium Limited"))
      (libsource (lib "Miscellaneous Devices") (part "Res2"))
    )
    (comp (ref "R44")
      (value "1K")
      (footprint "0805R")
      (description "Resistor")
      (fields (field (name "Comment") "RC0805JR-071KL") (field (name "PUBLISHER") "Altium Limited"))
      (libsource (lib "Miscellaneous Devices") (part "Res2"))
    )
    (comp (ref "R45")
      (value "470")
      (footprint "0805R")
      (description "Resistor")
      (fields (field (name "Comment") "RC0805JR-07470RL") (field (name "PUBLISHER") "Altium Limited"))
      (libsource (lib "Miscellaneous Devices") (part "Res2"))
    )
    (comp (ref "R46")
      (value "470")
      (footprint "0805R")
      (description "Resistor")
      (fields (field (name "Comment") "RC0805JR-07470RL") (field (name "PUBLISHER") "Altium Limited"))
      (libsource (lib "Miscellaneous Devices") (part "Res2"))
    )
    (comp (ref "R47")
      (value "470")
      (footprint "0805R")
      (description "Resistor")
      (fields (field (name "Comment") "RC0805JR-07470RL") (field (name "PUBLISHER") "Altium Limited"))
      (libsource (lib "Miscellaneous Devices") (part "Res2"))
    )
    (comp (ref "R48")
      (value "Res2")
      (footprint "0805R")
      (description "Resistor")
      (fields (field (name "ALTIUM_VALUE") "10K") (field (name "PUBLISHER") "Altium Limited"))
      (libsource (lib "Miscellaneous Devices") (part "Res2"))
    )
    (comp (ref "R49")
      (value "100K")
      (footprint "VR5")
      (description "Potentiometer")
      (fields (field (name "Comment") "3296W-1-104") (field (name "PUBLISHER") "Altium Limited"))
      (libsource (lib "Miscellaneous Devices") (part "RPot"))
    )
    (comp (ref "R50")
      (value "100M")
      (footprint "0805R")
      (description "Resistor")
      (fields (field (name "Comment") "RC0805JR-07100ML") (field (name "PUBLISHER") "Altium Limited"))
      (libsource (lib "Miscellaneous Devices") (part "Res2"))
    )
    (comp (ref "R51")
      (value "2K")
      (footprint "0805R")
      (description "Resistor")
      (fields (field (name "Comment") "RC0805JR-072KL") (field (name "PUBLISHER") "Altium Limited"))
      (libsource (lib "Miscellaneous Devices") (part "Res2"))
    )
    (comp (ref "R52")
      (value "5.6K")
      (footprint "0805R")
      (description "Resistor")
      (fields (field (name "Comment") "RC0805JR-075600RL") (field (name "PUBLISHER") "Altium Limited"))
      (libsource (lib "Miscellaneous Devices") (part "Res2"))
    )
    (comp (ref "R53")
      (value "1M")
      (footprint "0805R")
      (description "Resistor")
      (fields (field (name "Comment") "RC0805JR-071000KL") (field (name "PUBLISHER") "Altium Limited"))
      (libsource (lib "") (part "Res2_1"))
    )
    (comp (ref "R54")
      (value "68K")
      (footprint "0805R")
      (description "Resistor")
      (fields (field (name "Comment") "RC0805JR-0768KL") (field (name "PUBLISHER") "Altium Limited"))
      (libsource (lib "") (part "Res2_1"))
    )
    (comp (ref "R55")
      (value "RC0805JR-0768KL")
      (footprint "0805R")
      (description "Resistor")
      (fields (field (name "ALTIUM_VALUE") "68K") (field (name "PUBLISHER") "Altium Limited"))
      (libsource (lib "Miscellaneous Devices") (part "Res2"))
    )
    (comp (ref "R56")
      (value "2K")
      (footprint "0805R")
      (description "Resistor")
      (fields (field (name "Comment") "RC0805JR-072KL") (field (name "PUBLISHER") "Altium Limited"))
      (libsource (lib "Miscellaneous Devices") (part "Res2"))
    )
    (comp (ref "R57")
      (value "3296W-1-102")
      (footprint "VR5")
      (description "Potentiometer")
      (fields (field (name "ALTIUM_VALUE") "1K") (field (name "PUBLISHER") "Altium Limited"))
      (libsource (lib "Miscellaneous Devices") (part "RPot"))
    )
    (comp (ref "R58")
      (value "1K")
      (footprint "0805R")
      (description "Resistor")
      (fields (field (name "Comment") "RC0805JR-071KL") (field (name "PUBLISHER") "Altium Limited"))
      (libsource (lib "Miscellaneous Devices") (part "Res2"))
    )
    (comp (ref "R59")
      (value "1K")
      (footprint "0805R")
      (description "Resistor")
      (fields (field (name "Comment") "RC0805JR-071KL") (field (name "PUBLISHER") "Altium Limited"))
      (libsource (lib "Miscellaneous Devices") (part "Res2"))
    )
    (comp (ref "R60")
      (value "1K")
      (footprint "0805R")
      (description "Resistor")
      (fields (field (name "Comment") "RC0805JR-071KL") (field (name "PUBLISHER") "Altium Limited"))
      (libsource (lib "Miscellaneous Devices") (part "Res2"))
    )
    (comp (ref "R61")
      (value "10K")
      (footprint "0805R")
      (description "Resistor")
      (fields (field (name "Comment") "RC0805JR-0710KL") (field (name "PUBLISHER") "Altium Limited"))
      (libsource (lib "Miscellaneous Devices") (part "Res2"))
    )
    (comp (ref "R62")
      (value "RC0805JR-07470RL")
      (footprint "0805R")
      (description "Resistor")
      (fields (field (name "ALTIUM_VALUE") "470") (field (name "PUBLISHER") "Altium Limited"))
      (libsource (lib "") (part "Res2_3"))
    )
    (comp (ref "R63")
      (value "2K")
      (footprint "0805R")
      (description "Resistor")
      (fields (field (name "Comment") "RC0805JR-072KL") (field (name "PUBLISHER") "Altium Limited"))
      (libsource (lib "Miscellaneous Devices") (part "Res2"))
    )
    (comp (ref "R64")
      (value "2K")
      (footprint "0805R")
      (description "Resistor")
      (fields (field (name "Comment") "RC0805JR-072KL") (field (name "PUBLISHER") "Altium Limited"))
      (libsource (lib "Miscellaneous Devices") (part "Res2"))
    )
    (comp (ref "R65")
      (value "3.3K")
      (footprint "0805R")
      (description "Resistor")
      (fields (field (name "Comment") "RC0805JR-073300RL") (field (name "PUBLISHER") "Altium Limited"))
      (libsource (lib "Miscellaneous Devices") (part "Res2"))
    )
    (comp (ref "R66")
      (value "4.7K")
      (footprint "0805R")
      (description "Resistor")
      (fields (field (name "Comment") "RC0805JR-074700RL") (field (name "PUBLISHER") "Altium Limited"))
      (libsource (lib "Miscellaneous Devices") (part "Res2"))
    )
    (comp (ref "R67")
      (value "100M")
      (footprint "0805R")
      (description "Resistor")
      (fields (field (name "Comment") "RC0805JR-07100ML") (field (name "PUBLISHER") "Altium Limited"))
      (libsource (lib "") (part "Res2_3"))
    )
    (comp (ref "R68")
      (value "100K")
      (footprint "VR5")
      (description "Potentiometer")
      (fields (field (name "Comment") "3296W-1-104") (field (name "PUBLISHER") "Altium Limited"))
      (libsource (lib "Miscellaneous Devices") (part "RPot"))
    )
    (comp (ref "U1")
      (value "LM1117IMP-3.3/NOPB")
      (footprint "SOT223_N")
      (libsource (lib "Standard-V0.0") (part "LM1117IMP"))
    )
    (comp (ref "U2")
      (value "LM1117IMP-3.3/NOPB")
      (footprint "SOT223_N")
      (libsource (lib "Standard-V0.0") (part "LM1117IMP"))
    )
    (comp (ref "U3")
      (value "A05_S-1WR3")
      (footprint "A05_S-1WR3")
      (libsource (lib "Standard-V0.0") (part "A05_S-1WR3"))
    )
    (comp (ref "U4")
      (value "LM1117IMP-5.0/NOPB")
      (footprint "SOT223_N")
      (libsource (lib "Standard-V0.0") (part "LM1117IMP"))
    )
    (comp (ref "U5")
      (value "STC12C5620AD")
      (footprint "SOP20")
      (libsource (lib "Standard-V0.0") (part "STC12C5620AD"))
    )
    (comp (ref "U6") (value "6N137") (footprint "SO8_N") (libsource (lib "Standard-V0.0") (part "6N137")))
    (comp (ref "U7") (value "6N137") (footprint "SO8_N") (libsource (lib "") (part "6N137_1")))
    (comp (ref "U8") (value "LM2675") (footprint "TI-D8_N") (libsource (lib "TI_Sch_Lib") (part "LM2675")))
    (comp (ref "U9") (value "VO2630") (footprint "SO8_N") (libsource (lib "Standard-V0.0") (part "VO2630")))
    (comp (ref "U10") (value "VO2630") (footprint "SO8_N") (libsource (lib "Standard-V0.0") (part "VO2630")))
    (comp (ref "U11")
      (value "SNx5LBC184")
      (footprint "SO8_N")
      (libsource (lib "TI_Sch_Lib") (part "SNx5LBC184"))
    )
    (comp (ref "U12")
      (value "DAC7611U")
      (footprint "TI-D8_N")
      (libsource (lib "TI_Sch_Lib") (part "DAC7611"))
    )
    (comp (ref "U13") (value "TL431") (footprint "SOT-23-3") (libsource (lib "TI_Sch_Lib") (part "TL431")))
    (comp (ref "U14")
      (value "AD7124-8")
      (footprint "TI-RHB32-3150X3150TP_V")
      (libsource (lib "AD_Sch_Lib") (part "AD7124-8"))
    )
    (comp (ref "U15")
      (value "XTR111")
      (footprint "S-PDSO-G10")
      (libsource (lib "Standard-V0.0") (part "XTR111"))
    )
    (comp (ref "U16")
      (value "TL062ACD")
      (footprint "TI-D8_N")
      (fields (field (name "MANUFACTURER") "Texas Instruments"))
      (libsource (lib "TI Amplifiers and Linear Operational Amplifier General Purpose") (part "TL062ACD"))
    )
    (comp (ref "Y1")
      (value "XTAL")
      (footprint "11.0592MHz")
      (description "Crystal Oscillator")
      (fields (field (name "PUBLISHER") "Altium Limited"))
      (libsource (lib "Miscellaneous Devices") (part "XTAL"))
    )
  )
  (nets
    (net (code "1") (name "-15V") (class "Default")
      (node (ref "C20") (pin "1") (pinfunction "1_1") (pintype "passive"))
      (node (ref "C21") (pin "2") (pinfunction "2_2") (pintype "passive"))
      (node (ref "C62") (pin "1") (pinfunction "1_1") (pintype "passive"))
      (node (ref "C64") (pin "2") (pinfunction "2_2") (pintype "passive"))
      (node (ref "R49") (pin "1") (pinfunction "TOP_1") (pintype "passive"))
      (node (ref "R68") (pin "1") (pinfunction "TOP_1") (pintype "passive"))
      (node (ref "U16") (pin "4") (pinfunction "VCC-_4") (pintype "power_in"))
      (node (ref "U3") (pin "4") (pinfunction "-VO_4") (pintype "passive"))
    )
    (net (code "2") (name "/A1") (class "Default")
      (node (ref "R9") (pin "2") (pinfunction "2_2") (pintype "passive"))
      (node (ref "U5") (pin "15") (pinfunction "P1.3/ADC3_15") (pintype "passive"))
    )
    (net (code "3") (name "/A2") (class "Default")
      (node (ref "R10") (pin "2") (pinfunction "2_2") (pintype "passive"))
      (node (ref "U5") (pin "14") (pinfunction "P1.2/ADC2_14") (pintype "passive"))
    )
    (net (code "4") (name "/A3") (class "Default")
      (node (ref "R11") (pin "2") (pinfunction "2_2") (pintype "passive"))
      (node (ref "U5") (pin "13") (pinfunction "P1.1/ADC1/CLKOUT1_13") (pintype "passive"))
    )
    (net (code "5") (name "/A4") (class "Default")
      (node (ref "R12") (pin "2") (pinfunction "2_2") (pintype "passive"))
      (node (ref "U5") (pin "12") (pinfunction "P1.0/ADC0/CLKOUT0_12") (pintype "passive"))
    )
    (net (code "6") (name "/AIN0") (class "Default")
      (node (ref "C70") (pin "1") (pinfunction "1_1") (pintype "passive"))
      (node (ref "C71") (pin "1") (pinfunction "1_1") (pintype "passive"))
      (node (ref "R58") (pin "1") (pinfunction "1_1") (pintype "passive"))
      (node (ref "U14") (pin "4") (pinfunction "AIN0/IOUT/VBIAS_4") (pintype "passive"))
    )
    (net (code "7") (name "/AIN1") (class "Default")
      (node (ref "C71") (pin "2") (pinfunction "2_2") (pintype "passive"))
      (node (ref "C72") (pin "1") (pinfunction "1_1") (pintype "passive"))
      (node (ref "R53") (pin "2") (pinfunction "2_2") (pintype "passive"))
      (node (ref "R54") (pin "1") (pinfunction "1_1") (pintype "passive"))
      (node (ref "U14") (pin "5") (pinfunction "AIN1/IOUT/VBIAS_5") (pintype "passive"))
    )
    (net (code "8") (name "/AIN2") (class "Default")
      (node (ref "C73") (pin "1") (pinfunction "1_1") (pintype "passive"))
      (node (ref "C74") (pin "1") (pinfunction "1_1") (pintype "passive"))
      (node (ref "R59") (pin "1") (pinfunction "1_1") (pintype "passive"))
      (node (ref "U14") (pin "6") (pinfunction "AIN2/IOUT/VBIAS/P1_6") (pintype "passive"))
    )
    (net (code "9") (name "/AIN3") (class "Default")
      (node (ref "C74") (pin "2") (pinfunction "2_2") (pintype "passive"))
      (node (ref "C75") (pin "1") (pinfunction "1_1") (pintype "passive"))
      (node (ref "R60") (pin "1") (pinfunction "1_1") (pintype "passive"))
      (node (ref "U14") (pin "7") (pinfunction "AIN3/IOUT/VBIAS/P2_7") (pintype "passive"))
    )
    (net (code "10") (name "/AIN4") (class "Default")
      (node (ref "C56") (pin "1") (pinfunction "1_1") (pintype "passive"))
      (node (ref "C57") (pin "1") (pinfunction "1_1") (pintype "passive"))
      (node (ref "R42") (pin "1") (pinfunction "1_1") (pintype "passive"))
      (node (ref "U14") (pin "8") (pinfunction "AIN4/IOUT/VBIAS/P3_8") (pintype "passive"))
    )
    (net (code "11") (name "/AIN5") (class "Default")
      (node (ref "C57") (pin "2") (pinfunction "2_2") (pintype "passive"))
      (node (ref "C58") (pin "1") (pinfunction "1_1") (pintype "passive"))
      (node (ref "R43") (pin "1") (pinfunction "1_1") (pintype "passive"))
      (node (ref "U14") (pin "9") (pinfunction "AIN5/IOUT/VBIAS/P4_9") (pintype "passive"))
    )
    (net (code "12") (name "/AIN6") (class "Default")
      (node (ref "R48") (pin "1") (pinfunction "1_1") (pintype "passive"))
      (node (ref "U14") (pin "10") (pinfunction "AIN6/IOUT/VBIAS_10") (pintype "passive"))
    )
    (net (code "13") (name "/AIN7") (class "Default")
      (node (ref "C59") (pin "1") (pinfunction "1_1") (pintype "passive"))
      (node (ref "R44") (pin "1") (pinfunction "1_1") (pintype "passive"))
      (node (ref "U14") (pin "11") (pinfunction "AIN7/IOUT/VBIAS_11") (pintype "passive"))
    )
    (net (code "14") (name "/AIN8") (class "Default")
      (node (ref "C35") (pin "1") (pinfunction "1_1") (pintype "passive"))
      (node (ref "C36") (pin "1") (pinfunction "1_1") (pintype "passive"))
      (node (ref "R18") (pin "1") (pinfunction "1_1") (pintype "passive"))
      (node (ref "U14") (pin "14") (pinfunction "AIN8/IOUT/VBIAS_14") (pintype "passive"))
    )
    (net (code "15") (name "/AIN9") (class "Default")
      (node (ref "C36") (pin "2") (pinfunction "2_2") (pintype "passive"))
      (node (ref "C37") (pin "1") (pinfunction "1_1") (pintype "passive"))
      (node (ref "R19") (pin "1") (pinfunction "1_1") (pintype "passive"))
      (node (ref "U14") (pin "15") (pinfunction "AIN9/IOUT/VBIAS_15") (pintype "passive"))
    )
    (net (code "16") (name "/AIN10") (class "Default")
      (node (ref "C38") (pin "1") (pinfunction "1_1") (pintype "passive"))
      (node (ref "C39") (pin "1") (pinfunction "1_1") (pintype "passive"))
      (node (ref "R20") (pin "1") (pinfunction "1_1") (pintype "passive"))
      (node (ref "U14") (pin "16") (pinfunction "AIN10/IOUT/VBIAS_16") (pintype "passive"))
    )
    (net (code "17") (name "/AIN11") (class "Default")
      (node (ref "C39") (pin "2") (pinfunction "2_2") (pintype "passive"))
      (node (ref "C40") (pin "1") (pinfunction "1_1") (pintype "passive"))
      (node (ref "R21") (pin "1") (pinfunction "1_1") (pintype "passive"))
      (node (ref "U14") (pin "17") (pinfunction "AIN11/IOUT/VBIAS_17") (pintype "passive"))
    )
    (net (code "18") (name "/AIN12") (class "Default")
      (node (ref "C41") (pin "1") (pinfunction "1_1") (pintype "passive"))
      (node (ref "C42") (pin "1") (pinfunction "1_1") (pintype "passive"))
      (node (ref "R22") (pin "1") (pinfunction "1_1") (pintype "passive"))
      (node (ref "U14") (pin "18") (pinfunction "AIN12/IOUT/VBIAS_18") (pintype "passive"))
    )
    (net (code "19") (name "/AIN13") (class "Default")
      (node (ref "C42") (pin "2") (pinfunction "2_2") (pintype "passive"))
      (node (ref "C43") (pin "1") (pinfunction "1_1") (pintype "passive"))
      (node (ref "R23") (pin "1") (pinfunction "1_1") (pintype "passive"))
      (node (ref "U14") (pin "19") (pinfunction "AIN13/IOUT/VBIAS_19") (pintype "passive"))
    )
    (net (code "20") (name "/AIN14") (class "Default")
      (node (ref "C44") (pin "1") (pinfunction "1_1") (pintype "passive"))
      (node (ref "C45") (pin "1") (pinfunction "1_1") (pintype "passive"))
      (node (ref "R24") (pin "1") (pinfunction "1_1") (pintype "passive"))
      (node (ref "U14") (pin "20") (pinfunction "AIN14/IOUT/VBIAS/REFIN2+_20") (pintype "passive"))
    )
    (net (code "21") (name "/AIN15") (class "Default")
      (node (ref "C45") (pin "2") (pinfunction "2_2") (pintype "passive"))
      (node (ref "C46") (pin "1") (pinfunction "1_1") (pintype "passive"))
      (node (ref "R25") (pin "1") (pinfunction "1_1") (pintype "passive"))
      (node (ref "U14") (pin "21") (pinfunction "AIN15/IOUT/VBIAS/REFIN2-_21") (pintype "passive"))
    )
    (net (code "22") (name "/D1") (class "Default")
      (node (ref "R26") (pin "2") (pinfunction "2_2") (pintype "passive"))
      (node (ref "U12") (pin "2") (pinfunction "~{CS}_2") (pintype "passive"))
      (node (ref "U9") (pin "7") (pinfunction "VO1_7") (pintype "passive"))
    )
    (net (code "23") (name "/D2") (class "Default")
      (node (ref "R28") (pin "2") (pinfunction "2_2") (pintype "passive"))
      (node (ref "U12") (pin "3") (pinfunction "CLK_3") (pintype "passive"))
      (node (ref "U9") (pin "6") (pinfunction "VO2_6") (pintype "passive"))
    )
    (net (code "24") (name "/D3") (class "Default")
      (node (ref "R27") (pin "2") (pinfunction "2_2") (pintype "passive"))
      (node (ref "U10") (pin "7") (pinfunction "VO1_7") (pintype "passive"))
      (node (ref "U12") (pin "4") (pinfunction "SDI_4") (pintype "passive"))
    )
    (net (code "25") (name "/D4") (class "Default")
      (node (ref "R29") (pin "2") (pinfunction "2_2") (pintype "passive"))
      (node (ref "U10") (pin "6") (pinfunction "VO2_6") (pintype "passive"))
      (node (ref "U12") (pin "5") (pinfunction "~{LD}_5") (pintype "passive"))
    )
    (net (code "26") (name "/DIN") (class "Default")
      (node (ref "U14") (pin "29") (pinfunction "DIN_29") (pintype "passive"))
      (node (ref "U5") (pin "17") (pinfunction "P1.5/MOSI/ADC5_17") (pintype "passive"))
    )
    (net (code "27") (name "/DOUT") (class "Default")
      (node (ref "U14") (pin "28") (pinfunction "DOUT/~{RDY}_28") (pintype "passive"))
      (node (ref "U5") (pin "18") (pinfunction "P1.6/MISO/ADC6_18") (pintype "passive"))
    )
    (net (code "28") (name "/IS") (class "Default")
      (node (ref "Q1") (pin "3") (pinfunction "E_3") (pintype "passive"))
      (node (ref "R36") (pin "2") (pinfunction "2_2") (pintype "passive"))
      (node (ref "U15") (pin "2") (pinfunction "IS_2") (pintype "passive"))
    )
    (net (code "29") (name "/Iout") (class "Default")
      (node (ref "D10") (pin "2") (pinfunction "K_2") (pintype "passive"))
      (node (ref "P5") (pin "2") (pinfunction "2_2") (pintype "passive"))
      (node (ref "R34") (pin "1") (pinfunction "1_1") (pintype "passive"))
    )
    (net (code "30") (name "/PSW") (class "Default")
      (node (ref "R45") (pin "1") (pinfunction "1_1") (pintype "passive"))
      (node (ref "U14") (pin "25") (pinfunction "PSW_25") (pintype "passive"))
    )
    (net (code "31") (name "/REFIN1+") (class "Default")
      (node (ref "C53") (pin "1") (pinfunction "1_1") (pintype "passive"))
      (node (ref "C54") (pin "1") (pinfunction "1_1") (pintype "passive"))
      (node (ref "R40") (pin "1") (pinfunction "1_1") (pintype "passive"))
      (node (ref "U14") (pin "12") (pinfunction "REFIN1+_12") (pintype "passive"))
    )
    (net (code "32") (name "/REFIN1-") (class "Default")
      (node (ref "C54") (pin "2") (pinfunction "2_2") (pintype "passive"))
      (node (ref "C55") (pin "1") (pinfunction "1_1") (pintype "passive"))
      (node (ref "R41") (pin "1") (pinfunction "1_1") (pintype "passive"))
      (node (ref "U14") (pin "13") (pinfunction "REFIN1-_13") (pintype "passive"))
    )
    (net (code "33") (name "/REFOUT") (class "Default")
      (node (ref "NTC1") (pin "2") (pinfunction "2_2") (pintype "passive"))
      (node (ref "R53") (pin "1") (pinfunction "1_1") (pintype "passive"))
      (node (ref "R57") (pin "2") (pinfunction "BOT_2") (pintype "passive"))
      (node (ref "R59") (pin "2") (pinfunction "2_2") (pintype "passive"))
      (node (ref "U14") (pin "22") (pinfunction "REFOUT_22") (pintype "passive"))
    )
    (net (code "34") (name "/RS485+") (class "Default")
      (node (ref "R13") (pin "1") (pinfunction "1_1") (pintype "passive"))
      (node (ref "U11") (pin "6") (pinfunction "A_6") (pintype "passive"))
    )
    (net (code "35") (name "/RS485-") (class "Default")
      (node (ref "R14") (pin "2") (pinfunction "2_2") (pintype "passive"))
      (node (ref "U11") (pin "7") (pinfunction "B_7") (pintype "passive"))
    )
    (net (code "36") (name "/RxD") (class "Default")
      (node (ref "R7") (pin "1") (pinfunction "1_1") (pintype "passive"))
      (node (ref "U11") (pin "1") (pinfunction "R_1") (pintype "passive"))
      (node (ref "U7") (pin "2") (pinfunction "A_2") (pintype "passive"))
    )
    (net (code "37") (name "/SCLK") (class "Default")
      (node (ref "U14") (pin "30") (pinfunction "SCLK_30") (pintype "passive"))
      (node (ref "U5") (pin "19") (pinfunction "P1.7/SCLK/ADC7_19") (pintype "passive"))
    )
    (net (code "38") (name "/TxD") (class "Default")
      (node (ref "U11") (pin "4") (pinfunction "D_4") (pintype "passive"))
      (node (ref "U6") (pin "6") (pinfunction "VO_6") (pintype "passive"))
    )
    (net (code "39") (name "/VG") (class "Default")
      (node (ref "Q1") (pin "1") (pinfunction "C_1") (pintype "passive"))
      (node (ref "Q2") (pin "1") (pinfunction "G_1") (pintype "passive"))
      (node (ref "U15") (pin "3") (pinfunction "VG_3") (pintype "passive"))
    )
    (net (code "40") (name "/VOUT") (class "Default")
      (node (ref "R51") (pin "2") (pinfunction "2_2") (pintype "passive"))
      (node (ref "R64") (pin "1") (pinfunction "1_1") (pintype "passive"))
      (node (ref "U12") (pin "8") (pinfunction "VOUT_8") (pintype "passive"))
    )
    (net (code "41") (name "/VREGS") (class "Default")
      (node (ref "R37") (pin "2") (pinfunction "2_2") (pintype "passive"))
      (node (ref "R38") (pin "1") (pinfunction "1_1") (pintype "passive"))
      (node (ref "U15") (pin "4") (pinfunction "REGS_4") (pintype "passive"))
    )
    (net (code "42") (name "/~{CS}") (class "Default")
      (node (ref "U14") (pin "32") (pinfunction "~{C}S_32") (pintype "passive"))
      (node (ref "U5") (pin "16") (pinfunction "P1.4/~{SS}/ADC4_16") (pintype "passive"))
    )
    (net (code "43") (name "3.3AVDD") (class "Default")
      (node (ref "C13") (pin "1") (pinfunction "1_1") (pintype "passive"))
      (node (ref "C15") (pin "1") (pinfunction "1_1") (pintype "passive"))
      (node (ref "C66") (pin "1") (pinfunction "1_1") (pintype "passive"))
      (node (ref "C67") (pin "1") (pinfunction "1_1") (pintype "passive"))
      (node (ref "C68") (pin "1") (pinfunction "1_1") (pintype "passive"))
      (node (ref "C69") (pin "1") (pinfunction "1_1") (pintype "passive"))
      (node (ref "R47") (pin "1") (pinfunction "1_1") (pintype "passive"))
      (node (ref "U1") (pin "3") (pinfunction "VOUT_3") (pintype "passive"))
      (node (ref "U14") (pin "26") (pinfunction "AVDD_26") (pintype "passive"))
    )
    (net (code "44") (name "3.3VCC") (class "Default")
      (node (ref "C1") (pin "1") (pinfunction "1_1") (pintype "passive"))
      (node (ref "C14") (pin "1") (pinfunction "1_1") (pintype "passive"))
      (node (ref "C16") (pin "1") (pinfunction "1_1") (pintype "passive"))
      (node (ref "C3") (pin "1") (pinfunction "1_1") (pintype "passive"))
      (node (ref "C5") (pin "1") (pinfunction "1_1") (pintype "passive"))
      (node (ref "C76") (pin "1") (pinfunction "1_1") (pintype "passive"))
      (node (ref "C78") (pin "1") (pinfunction "1_1") (pintype "passive"))
      (node (ref "R1") (pin "1") (pinfunction "1_1") (pintype "passive"))
      (node (ref "R3") (pin "2") (pinfunction "2_2") (pintype "passive"))
      (node (ref "U14") (pin "2") (pinfunction "IOVDD_2") (pintype "passive"))
      (node (ref "U2") (pin "3") (pinfunction "VOUT_3") (pintype "passive"))
      (node (ref "U5") (pin "20") (pinfunction "VCC_20") (pintype "passive"))
      (node (ref "U7") (pin "8") (pinfunction "VCC_8") (pintype "passive"))
    )
    (net (code "45") (name "5VDD") (class "Default")
      (node (ref "C12") (pin "1") (pinfunction "1_1") (pintype "passive"))
      (node (ref "C17") (pin "2") (pinfunction "2_2") (pintype "passive"))
      (node (ref "C25") (pin "1") (pinfunction "1_1") (pintype "passive"))
      (node (ref "C26") (pin "1") (pinfunction "1_1") (pintype "passive"))
      (node (ref "C27") (pin "1") (pinfunction "1_1") (pintype "passive"))
      (node (ref "C28") (pin "1") (pinfunction "1_1") (pintype "passive"))
      (node (ref "C29") (pin "1") (pinfunction "1_1") (pintype "passive"))
      (node (ref "C30") (pin "1") (pinfunction "1_1") (pintype "passive"))
      (node (ref "C31") (pin "1") (pinfunction "1_1") (pintype "passive"))
      (node (ref "C32") (pin "1") (pinfunction "1_1") (pintype "passive"))
      (node (ref "C33") (pin "1") (pinfunction "1_1") (pintype "passive"))
      (node (ref "C34") (pin "1") (pinfunction "1_1") (pintype "passive"))
      (node (ref "D7") (pin "2") (pinfunction "K_2") (pintype "passive"))
      (node (ref "R15") (pin "1") (pinfunction "1_1") (pintype "passive"))
      (node (ref "R26") (pin "1") (pinfunction "1_1") (pintype "passive"))
      (node (ref "R27") (pin "1") (pinfunction "1_1") (pintype "passive"))
      (node (ref "R28") (pin "1") (pinfunction "1_1") (pintype "passive"))
      (node (ref "R29") (pin "1") (pinfunction "1_1") (pintype "passive"))
      (node (ref "R7") (pin "2") (pinfunction "2_2") (pintype "passive"))
      (node (ref "U10") (pin "8") (pinfunction "VCC_8") (pintype "passive"))
      (node (ref "U11") (pin "2") (pinfunction "~{RE}_2") (pintype "passive"))
      (node (ref "U11") (pin "3") (pinfunction "DE_3") (pintype "passive"))
      (node (ref "U11") (pin "8") (pinfunction "VCC_8") (pintype "passive"))
      (node (ref "U4") (pin "3") (pinfunction "VOUT_3") (pintype "passive"))
      (node (ref "U6") (pin "8") (pinfunction "VCC_8") (pintype "passive"))
      (node (ref "U9") (pin "8") (pinfunction "VCC_8") (pintype "passive"))
    )
    (net (code "46") (name "5VIN") (class "Default")
      (node (ref "C10") (pin "1") (pinfunction "1_1") (pintype "passive"))
      (node (ref "C22") (pin "1") (pinfunction "1_1") (pintype "passive"))
      (node (ref "C8") (pin "1") (pinfunction "1_1") (pintype "passive"))
      (node (ref "C9") (pin "1") (pinfunction "1_1") (pintype "passive"))
      (node (ref "D6") (pin "1") (pinfunction "A_1") (pintype "passive"))
      (node (ref "L1") (pin "2") (pinfunction "2_2") (pintype "passive"))
      (node (ref "U1") (pin "1") (pinfunction "VIN_1") (pintype "passive"))
      (node (ref "U2") (pin "1") (pinfunction "VIN_1") (pintype "passive"))
      (node (ref "U3") (pin "1") (pinfunction "VIN+_1") (pintype "passive"))
      (node (ref "U8") (pin "4") (pinfunction "FB_4") (pintype "passive"))
    )
    (net (code "47") (name "15V") (class "Default")
      (node (ref "C18") (pin "1") (pinfunction "1_1") (pintype "passive"))
      (node (ref "C19") (pin "1") (pinfunction "1_1") (pintype "passive"))
      (node (ref "C50") (pin "1") (pinfunction "1_1") (pintype "passive"))
      (node (ref "C51") (pin "1") (pinfunction "1_1") (pintype "passive"))
      (node (ref "C60") (pin "2") (pinfunction "2_2") (pintype "passive"))
      (node (ref "C61") (pin "2") (pinfunction "2_2") (pintype "passive"))
      (node (ref "C7") (pin "1") (pinfunction "1_1") (pintype "passive"))
      (node (ref "D11") (pin "2") (pinfunction "K_2") (pintype "passive"))
      (node (ref "R30") (pin "1") (pinfunction "1_1") (pintype "passive"))
      (node (ref "R49") (pin "2") (pinfunction "BOT_2") (pintype "passive"))
      (node (ref "R62") (pin "1") (pinfunction "1_1") (pintype "passive"))
      (node (ref "R68") (pin "2") (pinfunction "BOT_2") (pintype "passive"))
      (node (ref "U15") (pin "1") (pinfunction "VSP_1") (pintype "passive"))
      (node (ref "U16") (pin "8") (pinfunction "VCC+_8") (pintype "power_in"))
      (node (ref "U3") (pin "6") (pinfunction "+VO_6") (pintype "passive"))
      (node (ref "U4") (pin "1") (pinfunction "VIN_1") (pintype "passive"))
    )
    (net (code "48") (name "AGND") (class "Default")
      (node (ref "C1") (pin "2") (pinfunction "2_2") (pintype "passive"))
      (node (ref "C10") (pin "2") (pinfunction "2_2") (pintype "passive"))
      (node (ref "C13") (pin "2") (pinfunction "2_2") (pintype "passive"))
      (node (ref "C14") (pin "2") (pinfunction "2_2") (pintype "passive"))
      (node (ref "C15") (pin "2") (pinfunction "2_2") (pintype "passive"))
      (node (ref "C16") (pin "2") (pinfunction "2_2") (pintype "passive"))
      (node (ref "C2") (pin "2") (pinfunction "2_2") (pintype "passive"))
      (node (ref "C22") (pin "2") (pinfunction "2_2") (pintype "passive"))
      (node (ref "C23") (pin "2") (pinfunction "2_2") (pintype "passive"))
      (node (ref "C24") (pin "2") (pinfunction "2_2") (pintype "passive"))
      (node (ref "C3") (pin "2") (pinfunction "2_2") (pintype "passive"))
      (node (ref "C35") (pin "2") (pinfunction "2_2") (pintype "passive"))
      (node (ref "C37") (pin "2") (pinfunction "2_2") (pintype "passive"))
      (node (ref "C38") (pin "2") (pinfunction "2_2") (pintype "passive"))
      (node (ref "C4") (pin "2") (pinfunction "2_2") (pintype "passive"))
      (node (ref "C40") (pin "2") (pinfunction "2_2") (pintype "passive"))
      (node (ref "C41") (pin "2") (pinfunction "2_2") (pintype "passive"))
      (node (ref "C43") (pin "2") (pinfunction "2_2") (pintype "passive"))
      (node (ref "C44") (pin "2") (pinfunction "2_2") (pintype "passive"))
      (node (ref "C46") (pin "2") (pinfunction "2_2") (pintype "passive"))
      (node (ref "C52") (pin "2") (pinfunction "2_2") (pintype "passive"))
      (node (ref "C55") (pin "2") (pinfunction "2_2") (pintype "passive"))
      (node (ref "C56") (pin "2") (pinfunction "2_2") (pintype "passive"))
      (node (ref "C58") (pin "2") (pinfunction "2_2") (pintype "passive"))
      (node (ref "C59") (pin "2") (pinfunction "2_2") (pintype "passive"))
      (node (ref "C6") (pin "2") (pinfunction "2_2") (pintype "passive"))
      (node (ref "C63") (pin "1") (pinfunction "1_1") (pintype "passive"))
      (node (ref "C66") (pin "2") (pinfunction "2_2") (pintype "passive"))
      (node (ref "C67") (pin "2") (pinfunction "2_2") (pintype "passive"))
      (node (ref "C68") (pin "2") (pinfunction "2_2") (pintype "passive"))
      (node (ref "C69") (pin "2") (pinfunction "2_2") (pintype "passive"))
      (node (ref "C70") (pin "2") (pinfunction "2_2") (pintype "passive"))
      (node (ref "C72") (pin "2") (pinfunction "2_2") (pintype "passive"))
      (node (ref "C73") (pin "2") (pinfunction "2_2") (pintype "passive"))
      (node (ref "C75") (pin "2") (pinfunction "2_2") (pintype "passive"))
      (node (ref "C76") (pin "2") (pinfunction "2_2") (pintype "passive"))
      (node (ref "C78") (pin "2") (pinfunction "2_2") (pintype "passive"))
      (node (ref "C79") (pin "1") (pinfunction "1_1") (pintype "passive"))
      (node (ref "C8") (pin "2") (pinfunction "2_2") (pintype "passive"))
      (node (ref "C9") (pin "2") (pinfunction "2_2") (pintype "passive"))
      (node (ref "D1") (pin "2") (pinfunction "K_2") (pintype "passive"))
      (node (ref "D3") (pin "1") (pinfunction "A_1") (pintype "passive"))
      (node (ref "D4") (pin "1") (pinfunction "A_1") (pintype "passive"))
      (node (ref "D5") (pin "1") (pinfunction "A_1") (pintype "passive"))
      (node (ref "P1") (pin "1") (pinfunction "1_1") (pintype "passive"))
      (node (ref "R2") (pin "1") (pinfunction "1_1") (pintype "passive"))
      (node (ref "R46") (pin "1") (pinfunction "1_1") (pintype "passive"))
      (node (ref "R52") (pin "1") (pinfunction "1_1") (pintype "passive"))
      (node (ref "R55") (pin "1") (pinfunction "1_1") (pintype "passive"))
      (node (ref "R8") (pin "1") (pinfunction "1_1") (pintype "passive"))
      (node (ref "U1") (pin "2") (pinfunction "ADJ_2") (pintype "passive"))
      (node (ref "U10") (pin "2") (pinfunction "CATHODE_1_2") (pintype "passive"))
      (node (ref "U10") (pin "3") (pinfunction "CATHODE_2_3") (pintype "passive"))
      (node (ref "U14") (pin "23") (pinfunction "AVSS_23") (pintype "passive"))
      (node (ref "U14") (pin "3") (pinfunction "DGND_3") (pintype "passive"))
      (node (ref "U2") (pin "2") (pinfunction "ADJ_2") (pintype "passive"))
      (node (ref "U3") (pin "2") (pinfunction "VIN-_2") (pintype "passive"))
      (node (ref "U5") (pin "10") (pinfunction "GND_10") (pintype "passive"))
      (node (ref "U6") (pin "3") (pinfunction "C_3") (pintype "passive"))
      (node (ref "U7") (pin "5") (pinfunction "GND_5") (pintype "passive"))
      (node (ref "U8") (pin "6") (pinfunction "GND_6") (pintype "passive"))
      (node (ref "U9") (pin "2") (pinfunction "CATHODE_1_2") (pintype "passive"))
      (node (ref "U9") (pin "3") (pinfunction "CATHODE_2_3") (pintype "passive"))
    )
    (net (code "49") (name "Net-(C52-Pad1)") (class "Default")
      (node (ref "C52") (pin "1") (pinfunction "1_1") (pintype "passive"))
      (node (ref "C53") (pin "2") (pinfunction "2_2") (pintype "passive"))
      (node (ref "R39") (pin "1") (pinfunction "1_1") (pintype "passive"))
      (node (ref "R48") (pin "2") (pinfunction "2_2") (pintype "passive"))
    )
    (net (code "50") (name "Net-(D1-A)") (class "Default")
      (node (ref "D1") (pin "1") (pinfunction "A_1") (pintype "passive"))
      (node (ref "R1") (pin "2") (pinfunction "2_2") (pintype "passive"))
    )
    (net (code "51") (name "Net-(D2-A)") (class "Default")
      (node (ref "D2") (pin "1") (pinfunction "A_1") (pintype "passive"))
      (node (ref "F1") (pin "2") (pinfunction "2_2") (pintype "passive"))
    )
    (net (code "52") (name "Net-(D2-K)") (class "Default")
      (node (ref "D2") (pin "2") (pinfunction "K_2") (pintype "passive"))
      (node (ref "R5") (pin "2") (pinfunction "2_2") (pintype "passive"))
      (node (ref "R6") (pin "2") (pinfunction "2_2") (pintype "passive"))
    )
    (net (code "53") (name "Net-(D3-K)") (class "Default")
      (node (ref "C11") (pin "2") (pinfunction "2_2") (pintype "passive"))
      (node (ref "D3") (pin "2") (pinfunction "K_2") (pintype "passive"))
      (node (ref "L1") (pin "1") (pinfunction "1_1") (pintype "passive"))
      (node (ref "U8") (pin "8") (pinfunction "Vsw_8") (pintype "passive"))
    )
    (net (code "54") (name "Net-(D6-K)") (class "Default")
      (node (ref "D6") (pin "2") (pinfunction "K_2") (pintype "passive"))
      (node (ref "R8") (pin "2") (pinfunction "2_2") (pintype "passive"))
    )
    (net (code "55") (name "Net-(D7-A)") (class "Default")
      (node (ref "D7") (pin "1") (pinfunction "A_1") (pintype "passive"))
      (node (ref "D9") (pin "2") (pinfunction "K_2") (pintype "passive"))
      (node (ref "P4") (pin "1") (pinfunction "1_1") (pintype "passive"))
      (node (ref "R13") (pin "2") (pinfunction "2_2") (pintype "passive"))
      (node (ref "R15") (pin "2") (pinfunction "2_2") (pintype "passive"))
      (node (ref "R17") (pin "2") (pinfunction "2_2") (pintype "passive"))
    )
    (net (code "56") (name "Net-(D8-K)") (class "Default")
      (node (ref "D8") (pin "2") (pinfunction "K_2") (pintype "passive"))
      (node (ref "D9") (pin "1") (pinfunction "A_1") (pintype "passive"))
      (node (ref "P4") (pin "2") (pinfunction "2_2") (pintype "passive"))
      (node (ref "R14") (pin "1") (pinfunction "1_1") (pintype "passive"))
      (node (ref "R16") (pin "2") (pinfunction "2_2") (pintype "passive"))
      (node (ref "R17") (pin "1") (pinfunction "1_1") (pintype "passive"))
    )
    (net (code "57") (name "Net-(D11-A)") (class "Default")
      (node (ref "C49") (pin "1") (pinfunction "1_1") (pintype "passive"))
      (node (ref "D11") (pin "1") (pinfunction "A_1") (pintype "passive"))
      (node (ref "Q2") (pin "3") (pinfunction "S_3") (pintype "passive"))
      (node (ref "R34") (pin "2") (pinfunction "2_2") (pintype "passive"))
    )
    (net (code "58") (name "Net-(F1-Pad1)") (class "Default")
      (node (ref "F1") (pin "1") (pinfunction "1_1") (pintype "passive"))
      (node (ref "P1") (pin "4") (pinfunction "4_4") (pintype "passive"))
    )
    (net (code "59") (name "Net-(NTC1-Pad1)") (class "Default")
      (node (ref "NTC1") (pin "1") (pinfunction "1_1") (pintype "passive"))
      (node (ref "R52") (pin "2") (pinfunction "2_2") (pintype "passive"))
      (node (ref "R60") (pin "2") (pinfunction "2_2") (pintype "passive"))
    )
    (net (code "60") (name "Net-(P3-Pad1)") (class "Default")
      (node (ref "P3") (pin "1") (pinfunction "1_1") (pintype "passive"))
      (node (ref "R18") (pin "2") (pinfunction "2_2") (pintype "passive"))
    )
    (net (code "61") (name "Net-(P3-Pad2)") (class "Default")
      (node (ref "P3") (pin "2") (pinfunction "2_2") (pintype "passive"))
      (node (ref "R19") (pin "2") (pinfunction "2_2") (pintype "passive"))
    )
    (net (code "62") (name "Net-(P3-Pad3)") (class "Default")
      (node (ref "P3") (pin "3") (pinfunction "3_3") (pintype "passive"))
      (node (ref "R20") (pin "2") (pinfunction "2_2") (pintype "passive"))
    )
    (net (code "63") (name "Net-(P3-Pad4)") (class "Default")
      (node (ref "P3") (pin "4") (pinfunction "4_4") (pintype "passive"))
      (node (ref "R21") (pin "2") (pinfunction "2_2") (pintype "passive"))
    )
    (net (code "64") (name "Net-(P3-Pad5)") (class "Default")
      (node (ref "P3") (pin "5") (pinfunction "5_5") (pintype "passive"))
      (node (ref "R22") (pin "2") (pinfunction "2_2") (pintype "passive"))
    )
    (net (code "65") (name "Net-(P3-Pad6)") (class "Default")
      (node (ref "P3") (pin "6") (pinfunction "6_6") (pintype "passive"))
      (node (ref "R23") (pin "2") (pinfunction "2_2") (pintype "passive"))
    )
    (net (code "66") (name "Net-(P3-Pad7)") (class "Default")
      (node (ref "P3") (pin "7") (pinfunction "7_7") (pintype "passive"))
      (node (ref "R24") (pin "2") (pinfunction "2_2") (pintype "passive"))
    )
    (net (code "67") (name "Net-(P3-Pad8)") (class "Default")
      (node (ref "P3") (pin "8") (pinfunction "8_8") (pintype "passive"))
      (node (ref "R25") (pin "2") (pinfunction "2_2") (pintype "passive"))
    )
    (net (code "68") (name "Net-(P6-Pad1)") (class "Default")
      (node (ref "P6") (pin "1") (pinfunction "1_1") (pintype "passive"))
      (node (ref "R47") (pin "2") (pinfunction "2_2") (pintype "passive"))
    )
    (net (code "69") (name "Net-(P6-Pad2)") (class "Default")
      (node (ref "P6") (pin "2") (pinfunction "2_2") (pintype "passive"))
      (node (ref "R35") (pin "2") (pinfunction "2_2") (pintype "passive"))
      (node (ref "R39") (pin "2") (pinfunction "2_2") (pintype "passive"))
      (node (ref "R40") (pin "2") (pinfunction "2_2") (pintype "passive"))
    )
    (net (code "70") (name "Net-(P6-Pad3)") (class "Default")
      (node (ref "P6") (pin "3") (pinfunction "3_3") (pintype "passive"))
      (node (ref "R35") (pin "1") (pinfunction "1_1") (pintype "passive"))
      (node (ref "R41") (pin "2") (pinfunction "2_2") (pintype "passive"))
    )
    (net (code "71") (name "Net-(P6-Pad4)") (class "Default")
      (node (ref "P6") (pin "4") (pinfunction "4_4") (pintype "passive"))
      (node (ref "R42") (pin "2") (pinfunction "2_2") (pintype "passive"))
    )
    (net (code "72") (name "Net-(P6-Pad5)") (class "Default")
      (node (ref "P6") (pin "5") (pinfunction "5_5") (pintype "passive"))
      (node (ref "R43") (pin "2") (pinfunction "2_2") (pintype "passive"))
    )
    (net (code "73") (name "Net-(P6-Pad6)") (class "Default")
      (node (ref "P6") (pin "6") (pinfunction "6_6") (pintype "passive"))
      (node (ref "R44") (pin "2") (pinfunction "2_2") (pintype "passive"))
    )
    (net (code "74") (name "Net-(P6-Pad7)") (class "Default")
      (node (ref "P6") (pin "7") (pinfunction "7_7") (pintype "passive"))
      (node (ref "R45") (pin "2") (pinfunction "2_2") (pintype "passive"))
    )
    (net (code "75") (name "Net-(P6-Pad8)") (class "Default")
      (node (ref "P6") (pin "8") (pinfunction "8_8") (pintype "passive"))
      (node (ref "R46") (pin "2") (pinfunction "2_2") (pintype "passive"))
    )
    (net (code "76") (name "Net-(Q1-B)") (class "Default")
      (node (ref "Q1") (pin "2") (pinfunction "B_2") (pintype "passive"))
      (node (ref "Q2") (pin "2") (pinfunction "D_2") (pintype "passive"))
      (node (ref "R36") (pin "1") (pinfunction "1_1") (pintype "passive"))
    )
    (net (code "77") (name "Net-(Q3-B)") (class "Default")
      (node (ref "Q3") (pin "2") (pinfunction "B_2") (pintype "passive"))
      (node (ref "R61") (pin "1") (pinfunction "1_1") (pintype "passive"))
    )
    (net (code "78") (name "Net-(Q3-C)") (class "Default")
      (node (ref "Q3") (pin "1") (pinfunction "C_1") (pintype "passive"))
      (node (ref "R62") (pin "2") (pinfunction "2_2") (pintype "passive"))
    )
    (net (code "79") (name "Net-(Q3-E)") (class "Default")
      (node (ref "P7") (pin "1") (pinfunction "1_1") (pintype "passive"))
      (node (ref "Q3") (pin "3") (pinfunction "E_3") (pintype "passive"))
      (node (ref "R56") (pin "1") (pinfunction "1_1") (pintype "passive"))
    )
    (net (code "80") (name "Net-(R49-TAP)") (class "Default")
      (node (ref "R49") (pin "3") (pinfunction "TAP_3") (pintype "passive"))
      (node (ref "R50") (pin "2") (pinfunction "2_2") (pintype "passive"))
    )
    (net (code "81") (name "Net-(R57-TAP)") (class "Default")
      (node (ref "R57") (pin "3") (pinfunction "TAP_3") (pintype "passive"))
      (node (ref "R58") (pin "2") (pinfunction "2_2") (pintype "passive"))
    )
    (net (code "82") (name "Net-(R57-TOP)") (class "Default")
      (node (ref "R54") (pin "2") (pinfunction "2_2") (pintype "passive"))
      (node (ref "R55") (pin "2") (pinfunction "2_2") (pintype "passive"))
      (node (ref "R57") (pin "1") (pinfunction "TOP_1") (pintype "passive"))
    )
    (net (code "83") (name "Net-(R65-Pad1)") (class "Default")
      (node (ref "R65") (pin "1") (pinfunction "1_1") (pintype "passive"))
      (node (ref "R66") (pin "2") (pinfunction "2_2") (pintype "passive"))
      (node (ref "R67") (pin "1") (pinfunction "1_1") (pintype "passive"))
    )
    (net (code "84") (name "Net-(R68-TAP)") (class "Default")
      (node (ref "R67") (pin "2") (pinfunction "2_2") (pintype "passive"))
      (node (ref "R68") (pin "3") (pinfunction "TAP_3") (pintype "passive"))
    )
    (net (code "85") (name "Net-(U5-RST)") (class "Default")
      (node (ref "C5") (pin "2") (pinfunction "2_2") (pintype "passive"))
      (node (ref "R2") (pin "2") (pinfunction "2_2") (pintype "passive"))
      (node (ref "U5") (pin "1") (pinfunction "RST_1") (pintype "passive"))
    )
    (net (code "86") (name "Net-(U5-RxD{slash}P3.0)") (class "Default")
      (node (ref "P2") (pin "2") (pinfunction "2_2") (pintype "passive"))
      (node (ref "R3") (pin "1") (pinfunction "1_1") (pintype "passive"))
      (node (ref "U5") (pin "2") (pinfunction "RxD/P3.0_2") (pintype "passive"))
      (node (ref "U7") (pin "6") (pinfunction "VO_6") (pintype "passive"))
    )
    (net (code "87") (name "Net-(U5-TxD{slash}P3.1)") (class "Default")
      (node (ref "P2") (pin "1") (pinfunction "1_1") (pintype "passive"))
      (node (ref "R4") (pin "1") (pinfunction "1_1") (pintype "passive"))
      (node (ref "U5") (pin "3") (pinfunction "TxD/P3.1_3") (pintype "passive"))
    )
    (net (code "88") (name "Net-(U5-XTAL1)") (class "Default")
      (node (ref "C6") (pin "1") (pinfunction "1_1") (pintype "passive"))
      (node (ref "U5") (pin "5") (pinfunction "XTAL1_5") (pintype "passive"))
      (node (ref "Y1") (pin "1") (pinfunction "OSC1_1") (pintype "passive"))
    )
    (net (code "89") (name "Net-(U5-XTAL2)") (class "Default")
      (node (ref "C2") (pin "1") (pinfunction "1_1") (pintype "passive"))
      (node (ref "U5") (pin "4") (pinfunction "XTAL2_4") (pintype "passive"))
      (node (ref "Y1") (pin "2") (pinfunction "OSC2_2") (pintype "passive"))
    )
    (net (code "90") (name "Net-(U6-A)") (class "Default")
      (node (ref "R4") (pin "2") (pinfunction "2_2") (pintype "passive"))
      (node (ref "U6") (pin "2") (pinfunction "A_2") (pintype "passive"))
    )
    (net (code "91") (name "Net-(U8-CB)") (class "Default")
      (node (ref "C11") (pin "1") (pinfunction "1_1") (pintype "passive"))
      (node (ref "U8") (pin "1") (pinfunction "CB_1") (pintype "passive"))
    )
    (net (code "92") (name "Net-(U9-ANODE_1)") (class "Default")
      (node (ref "R9") (pin "1") (pinfunction "1_1") (pintype "passive"))
      (node (ref "U9") (pin "1") (pinfunction "ANODE_1_1") (pintype "passive"))
    )
    (net (code "93") (name "Net-(U9-ANODE_2)") (class "Default")
      (node (ref "R10") (pin "1") (pinfunction "1_1") (pintype "passive"))
      (node (ref "U9") (pin "4") (pinfunction "ANODE_2_4") (pintype "passive"))
    )
    (net (code "94") (name "Net-(U10-ANODE_1)") (class "Default")
      (node (ref "R11") (pin "1") (pinfunction "1_1") (pintype "passive"))
      (node (ref "U10") (pin "1") (pinfunction "ANODE_1_1") (pintype "passive"))
    )
    (net (code "95") (name "Net-(U10-ANODE_2)") (class "Default")
      (node (ref "R12") (pin "1") (pinfunction "1_1") (pintype "passive"))
      (node (ref "U10") (pin "4") (pinfunction "ANODE_2_4") (pintype "passive"))
    )
    (net (code "96") (name "Net-(U13-REF)") (class "Default")
      (node (ref "R31") (pin "1") (pinfunction "1_1") (pintype "passive"))
      (node (ref "R32") (pin "2") (pinfunction "2_2") (pintype "passive"))
      (node (ref "R33") (pin "1") (pinfunction "1_1") (pintype "passive"))
      (node (ref "U13") (pin "2") (pinfunction "REF_2") (pintype "passive"))
    )
    (net (code "97") (name "Net-(U14-REGCAPA)") (class "Default")
      (node (ref "C79") (pin "2") (pinfunction "2_2") (pintype "passive"))
      (node (ref "U14") (pin "24") (pinfunction "REGCAPA_24") (pintype "passive"))
    )
    (net (code "98") (name "Net-(U14-REGCAPD)") (class "Default")
      (node (ref "C63") (pin "2") (pinfunction "2_2") (pintype "passive"))
      (node (ref "U14") (pin "1") (pinfunction "REGCAPD_1") (pintype "passive"))
    )
    (net (code "99") (name "Net-(U15-SET)") (class "Default")
      (node (ref "R63") (pin "2") (pinfunction "2_2") (pintype "passive"))
      (node (ref "U15") (pin "7") (pinfunction "SET_7") (pintype "passive"))
    )
    (net (code "100") (name "Net-(U15-VIN)") (class "Default")
      (node (ref "C77") (pin "2") (pinfunction "2_2") (pintype "passive"))
      (node (ref "R64") (pin "2") (pinfunction "2_2") (pintype "passive"))
      (node (ref "R65") (pin "2") (pinfunction "2_2") (pintype "passive"))
      (node (ref "U15") (pin "6") (pinfunction "VIN_6") (pintype "passive"))
    )
    (net (code "101") (name "Net-(U16A-IN1+)") (class "Default")
      (node (ref "C65") (pin "1") (pinfunction "1_1") (pintype "passive"))
      (node (ref "R51") (pin "1") (pinfunction "1_1") (pintype "passive"))
      (node (ref "U16") (pin "3") (pinfunction "IN1+_3") (pintype "input"))
    )
    (net (code "102") (name "Net-(U16A-IN1-)") (class "Default")
      (node (ref "R50") (pin "1") (pinfunction "1_1") (pintype "passive"))
      (node (ref "R56") (pin "2") (pinfunction "2_2") (pintype "passive"))
      (node (ref "U16") (pin "2") (pinfunction "IN1-_2") (pintype "input"))
    )
    (net (code "103") (name "Net-(U16A-OUT1)") (class "Default")
      (node (ref "R61") (pin "2") (pinfunction "2_2") (pintype "passive"))
      (node (ref "U16") (pin "1") (pinfunction "OUT1_1") (pintype "output"))
    )
    (net (code "104") (name "SGND") (class "Default")
      (node (ref "C12") (pin "2") (pinfunction "2_2") (pintype "passive"))
      (node (ref "C17") (pin "1") (pinfunction "1_1") (pintype "passive"))
      (node (ref "C18") (pin "2") (pinfunction "2_2") (pintype "passive"))
      (node (ref "C19") (pin "2") (pinfunction "2_2") (pintype "passive"))
      (node (ref "C20") (pin "2") (pinfunction "2_2") (pintype "passive"))
      (node (ref "C21") (pin "1") (pinfunction "1_1") (pintype "passive"))
      (node (ref "C25") (pin "2") (pinfunction "2_2") (pintype "passive"))
      (node (ref "C26") (pin "2") (pinfunction "2_2") (pintype "passive"))
      (node (ref "C27") (pin "2") (pinfunction "2_2") (pintype "passive"))
      (node (ref "C28") (pin "2") (pinfunction "2_2") (pintype "passive"))
      (node (ref "C29") (pin "2") (pinfunction "2_2") (pintype "passive"))
      (node (ref "C30") (pin "2") (pinfunction "2_2") (pintype "passive"))
      (node (ref "C31") (pin "2") (pinfunction "2_2") (pintype "passive"))
      (node (ref "C32") (pin "2") (pinfunction "2_2") (pintype "passive"))
      (node (ref "C33") (pin "2") (pinfunction "2_2") (pintype "passive"))
      (node (ref "C34") (pin "2") (pinfunction "2_2") (pintype "passive"))
      (node (ref "C47") (pin "2") (pinfunction "2_2") (pintype "passive"))
      (node (ref "C48") (pin "1") (pinfunction "1_1") (pintype "passive"))
      (node (ref "C49") (pin "2") (pinfunction "2_2") (pintype "passive"))
      (node (ref "C50") (pin "2") (pinfunction "2_2") (pintype "passive"))
      (node (ref "C51") (pin "2") (pinfunction "2_2") (pintype "passive"))
      (node (ref "C60") (pin "1") (pinfunction "1_1") (pintype "passive"))
      (node (ref "C61") (pin "1") (pinfunction "1_1") (pintype "passive"))
      (node (ref "C62") (pin "2") (pinfunction "2_2") (pintype "passive"))
      (node (ref "C64") (pin "1") (pinfunction "1_1") (pintype "passive"))
      (node (ref "C65") (pin "2") (pinfunction "2_2") (pintype "passive"))
      (node (ref "C7") (pin "2") (pinfunction "2_2") (pintype "passive"))
      (node (ref "C77") (pin "1") (pinfunction "1_1") (pintype "passive"))
      (node (ref "D10") (pin "1") (pinfunction "A_1") (pintype "passive"))
      (node (ref "D8") (pin "1") (pinfunction "A_1") (pintype "passive"))
      (node (ref "P5") (pin "1") (pinfunction "1_1") (pintype "passive"))
      (node (ref "P7") (pin "2") (pinfunction "2_2") (pintype "passive"))
      (node (ref "R16") (pin "1") (pinfunction "1_1") (pintype "passive"))
      (node (ref "R31") (pin "2") (pinfunction "2_2") (pintype "passive"))
      (node (ref "R33") (pin "2") (pinfunction "2_2") (pintype "passive"))
      (node (ref "R38") (pin "2") (pinfunction "2_2") (pintype "passive"))
      (node (ref "R63") (pin "1") (pinfunction "1_1") (pintype "passive"))
      (node (ref "U10") (pin "5") (pinfunction "GND_5") (pintype "passive"))
      (node (ref "U11") (pin "5") (pinfunction "GND_5") (pintype "passive"))
      (node (ref "U12") (pin "7") (pinfunction "GND_7") (pintype "passive"))
      (node (ref "U13") (pin "3") (pinfunction "ANODE_3") (pintype "passive"))
      (node (ref "U15") (pin "10") (pinfunction "GND_10") (pintype "passive"))
      (node (ref "U15") (pin "9") (pinfunction "OD_9") (pintype "passive"))
      (node (ref "U3") (pin "5") (pinfunction "GND_5") (pintype "passive"))
      (node (ref "U4") (pin "2") (pinfunction "ADJ_2") (pintype "passive"))
      (node (ref "U6") (pin "5") (pinfunction "GND_5") (pintype "passive"))
      (node (ref "U7") (pin "3") (pinfunction "C_3") (pintype "passive"))
      (node (ref "U9") (pin "5") (pinfunction "GND_5") (pintype "passive"))
    )
    (net (code "105") (name "VBIAS") (class "Default")
      (node (ref "R30") (pin "2") (pinfunction "2_2") (pintype "passive"))
      (node (ref "R32") (pin "1") (pinfunction "1_1") (pintype "passive"))
      (node (ref "R66") (pin "1") (pinfunction "1_1") (pintype "passive"))
      (node (ref "U13") (pin "1") (pinfunction "CATHODE_1") (pintype "passive"))
    )
    (net (code "106") (name "VIN+") (class "Default")
      (node (ref "C23") (pin "1") (pinfunction "1_1") (pintype "passive"))
      (node (ref "C24") (pin "1") (pinfunction "1_1") (pintype "passive"))
      (node (ref "C4") (pin "1") (pinfunction "1_1") (pintype "passive"))
      (node (ref "D4") (pin "2") (pinfunction "K_2") (pintype "passive"))
      (node (ref "D5") (pin "2") (pinfunction "K_2") (pintype "passive"))
      (node (ref "R5") (pin "1") (pinfunction "1_1") (pintype "passive"))
      (node (ref "R6") (pin "1") (pinfunction "1_1") (pintype "passive"))
      (node (ref "U8") (pin "7") (pinfunction "VIN_7") (pintype "passive"))
    )
    (net (code "107") (name "VREGF") (class "Default")
      (node (ref "C47") (pin "1") (pinfunction "1_1") (pintype "passive"))
      (node (ref "C48") (pin "2") (pinfunction "2_2") (pintype "passive"))
      (node (ref "R37") (pin "1") (pinfunction "1_1") (pintype "passive"))
      (node (ref "U12") (pin "1") (pinfunction "VDD_1") (pintype "passive"))
      (node (ref "U12") (pin "6") (pinfunction "~{CLR}_6") (pintype "passive"))
      (node (ref "U15") (pin "5") (pinfunction "REGF_5") (pintype "passive"))
    )
    (net (code "108") (name "unconnected-(P1-Pad2)") (class "Default")
      (node (ref "P1") (pin "2") (pinfunction "2_2") (pintype "passive"))
    )
    (net (code "109") (name "unconnected-(P1-Pad3)") (class "Default")
      (node (ref "P1") (pin "3") (pinfunction "3_3") (pintype "passive"))
    )
    (net (code "110") (name "unconnected-(U3-NC-Pad3)") (class "Default")
      (node (ref "U3") (pin "3") (pinfunction "NC_3") (pintype "passive"))
    )
    (net (code "111") (name "unconnected-(U5-ECI{slash}T0{slash}P3.4-Pad8)") (class "Default")
      (node (ref "U5") (pin "8") (pinfunction "ECI/T0/P3.4_8") (pintype "passive"))
    )
    (net (code "112") (name "unconnected-(U5-P3.7{slash}PCA0{slash}PWM0-Pad11)") (class "Default")
      (node (ref "U5") (pin "11") (pinfunction "P3.7/PCA0/PWM0_11") (pintype "passive"))
    )
    (net (code "113") (name "unconnected-(U5-PWM1{slash}PCA1{slash}T1{slash}P3.5-Pad9)") (class "Default")
      (node (ref "U5") (pin "9") (pinfunction "PWM1/PCA1/T1/P3.5_9") (pintype "passive"))
    )
    (net (code "114") (name "unconnected-(U5-~{INT0}{slash}P3.2-Pad6)") (class "Default")
      (node (ref "U5") (pin "6") (pinfunction "~{INT0}/P3.2_6") (pintype "passive"))
    )
    (net (code "115") (name "unconnected-(U5-~{INT1}{slash}P3.3-Pad7)") (class "Default")
      (node (ref "U5") (pin "7") (pinfunction "~{INT1}/P3.3_7") (pintype "passive"))
    )
    (net (code "116") (name "unconnected-(U6-NC-Pad1)") (class "Default")
      (node (ref "U6") (pin "1") (pinfunction "NC_1") (pintype "passive"))
    )
    (net (code "117") (name "unconnected-(U6-NC-Pad4)") (class "Default")
      (node (ref "U6") (pin "4") (pinfunction "NC_4") (pintype "passive"))
    )
    (net (code "118") (name "unconnected-(U6-VE-Pad7)") (class "Default")
      (node (ref "U6") (pin "7") (pinfunction "VE_7") (pintype "passive"))
    )
    (net (code "119") (name "unconnected-(U7-NC-Pad1)") (class "Default")
      (node (ref "U7") (pin "1") (pinfunction "NC_1") (pintype "passive"))
    )
    (net (code "120") (name "unconnected-(U7-NC-Pad4)") (class "Default")
      (node (ref "U7") (pin "4") (pinfunction "NC_4") (pintype "passive"))
    )
    (net (code "121") (name "unconnected-(U7-VE-Pad7)") (class "Default")
      (node (ref "U7") (pin "7") (pinfunction "VE_7") (pintype "passive"))
    )
    (net (code "122") (name "unconnected-(U8-NC-Pad2)") (class "Default")
      (node (ref "U8") (pin "2") (pinfunction "NC_2") (pintype "passive"))
    )
    (net (code "123") (name "unconnected-(U8-NC-Pad3)") (class "Default")
      (node (ref "U8") (pin "3") (pinfunction "NC_3") (pintype "passive"))
    )
    (net (code "124") (name "unconnected-(U8-ON{slash}~{OFF}-Pad5)") (class "Default")
      (node (ref "U8") (pin "5") (pinfunction "ON/~{OFF}_5") (pintype "passive"))
    )
    (net (code "125") (name "unconnected-(U14-CLK-Pad31)") (class "Default")
      (node (ref "U14") (pin "31") (pinfunction "CLK_31") (pintype "passive"))
    )
    (net (code "126") (name "unconnected-(U14-~{SYNC}-Pad27)") (class "Default")
      (node (ref "U14") (pin "27") (pinfunction "~{SYNC}_27") (pintype "passive"))
    )
    (net (code "127") (name "unconnected-(U15-~{EF}-Pad8)") (class "Default")
      (node (ref "U15") (pin "8") (pinfunction "~{EF}_8") (pintype "passive"))
    )
  )
)
